# R3D900.net
KiCad netlist of a schematic drawn in Altium Designer
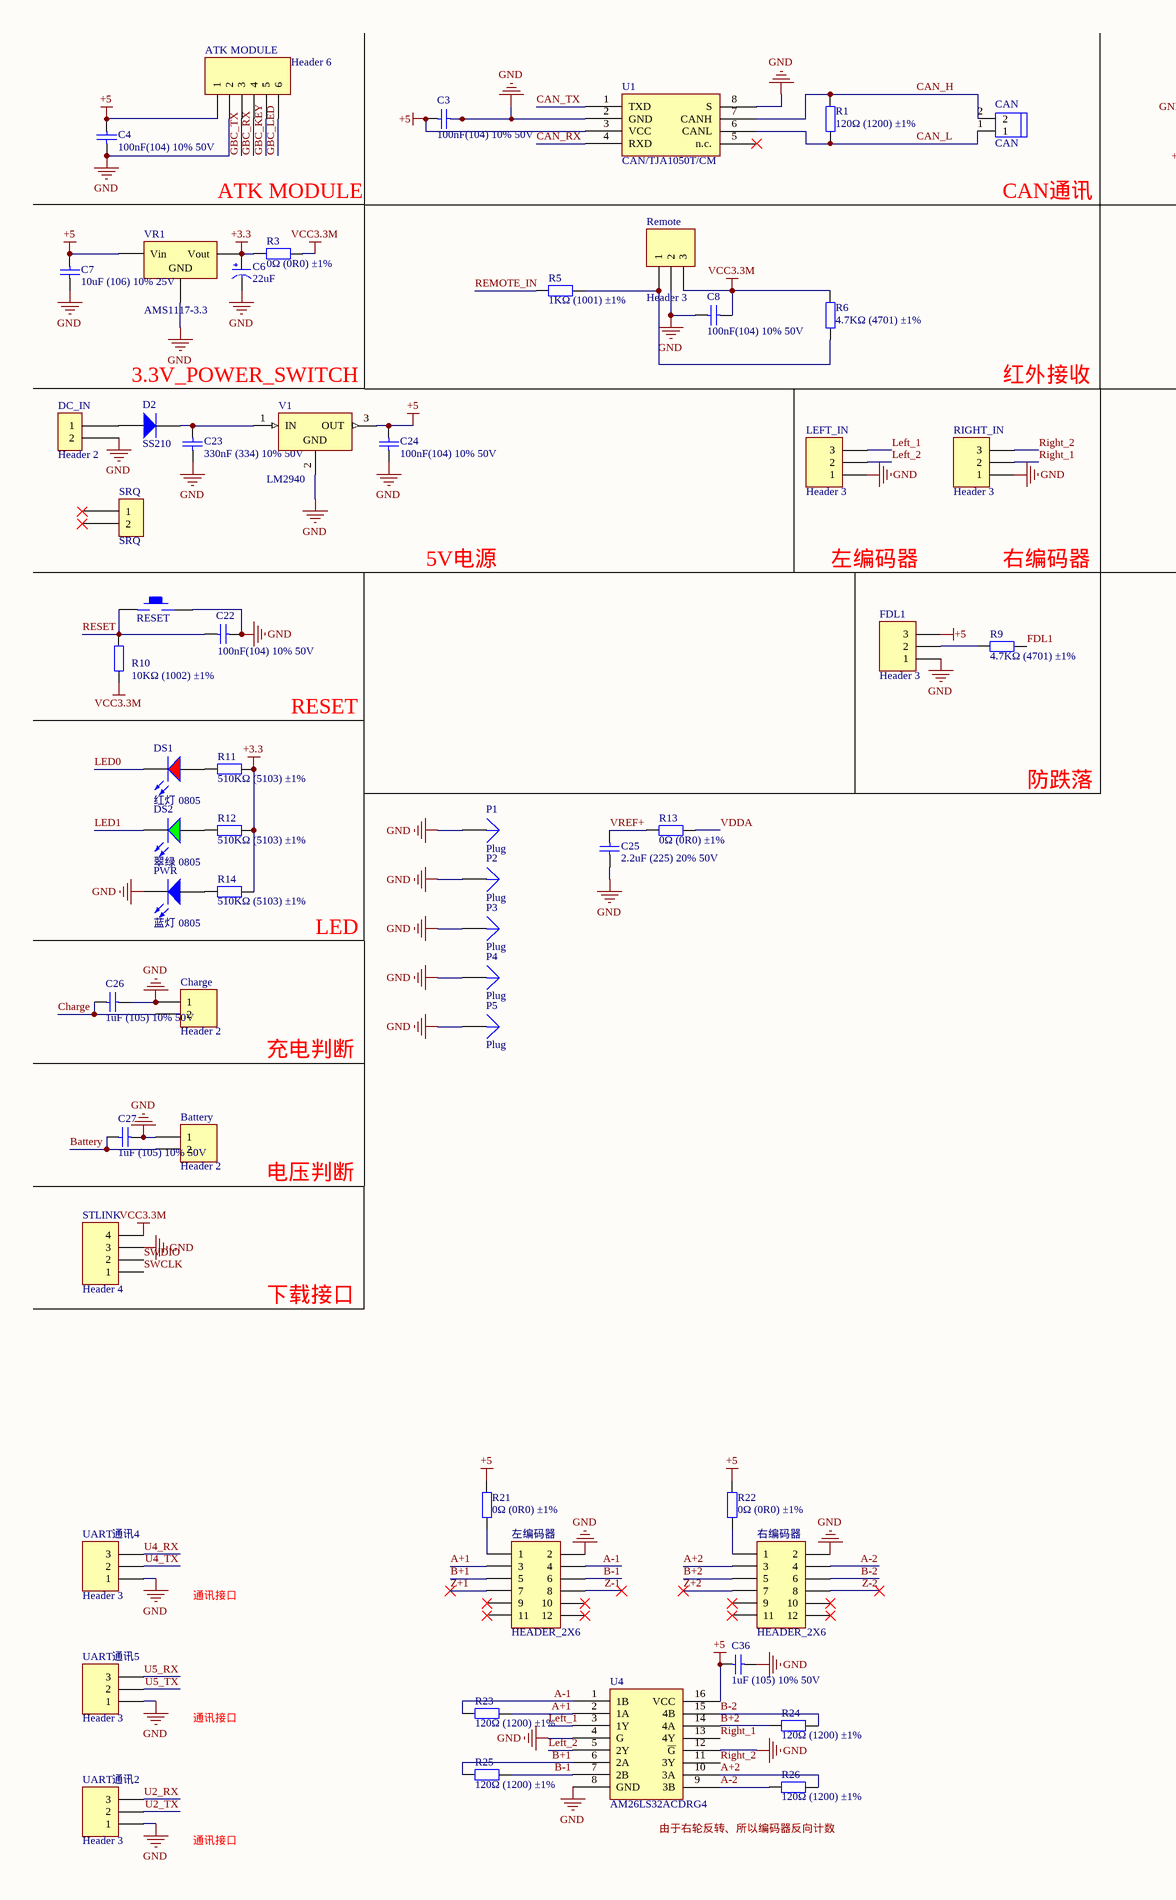
[diagram p0: R3D900.SchDoc, left]
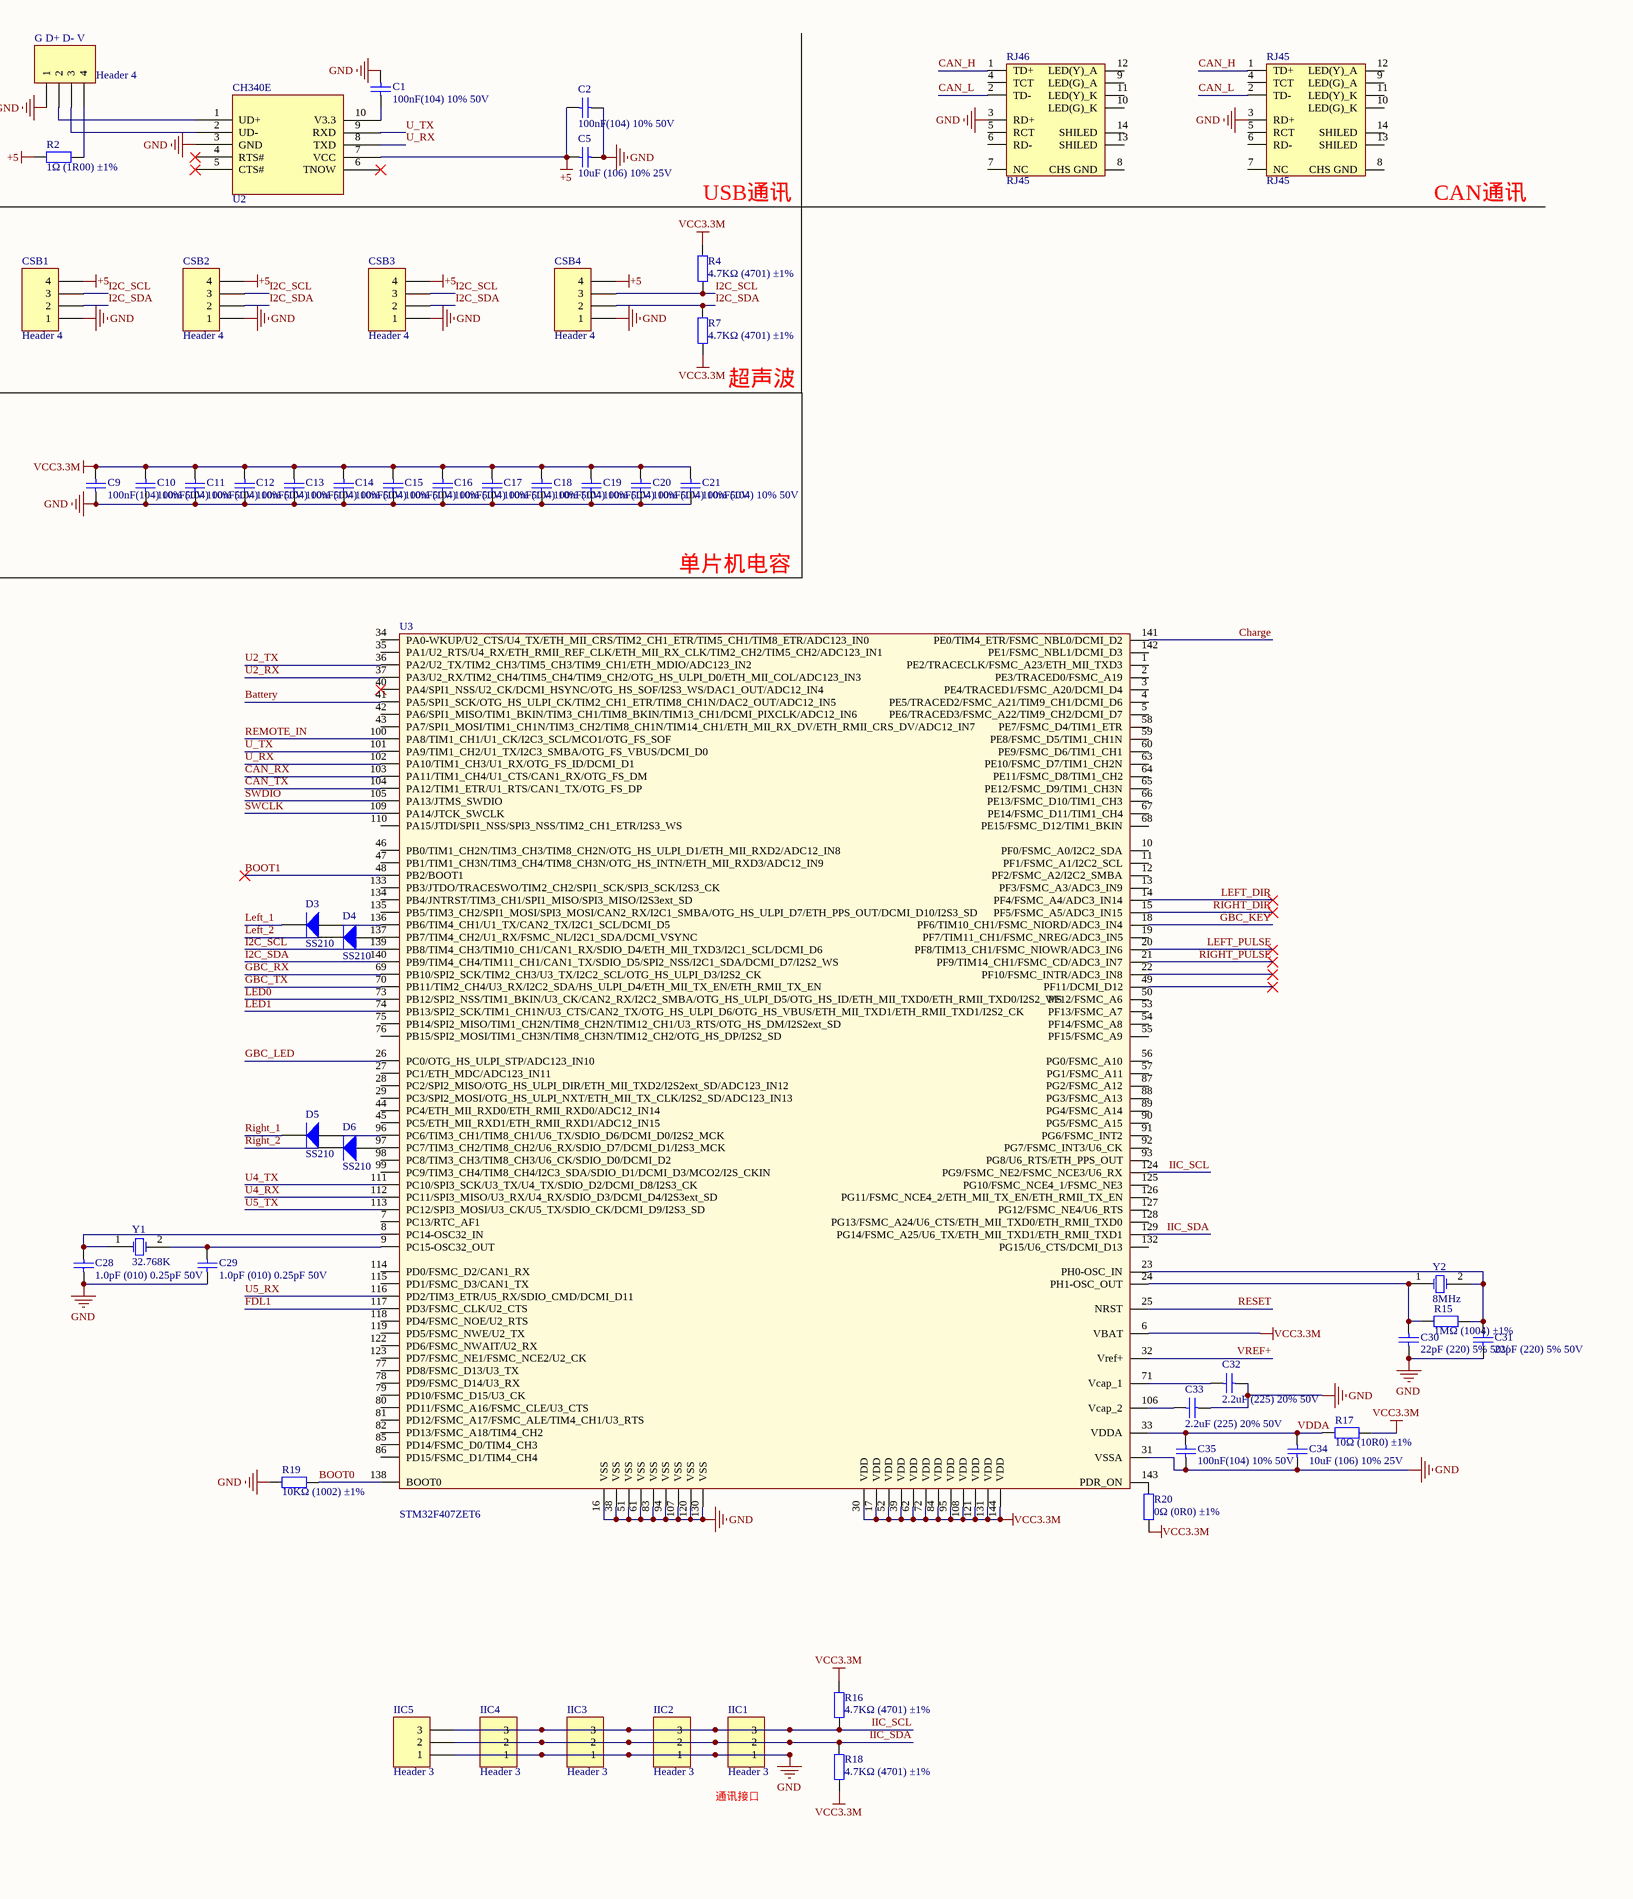
[diagram p1: R3D900.SchDoc, right]

(export (version "E")
  (design (tool "Eeschema 10.0.6"))
  (components
    (comp (ref "ATK MODULE")
      (value "Header 6")
      (footprint "HDR1X6")
      (description "Header, 6-Pin")
      (fields (field (name "PUBLISHER") "Altium Limited"))
      (libsource (lib "Miscellaneous Connectors") (part "Header 6"))
    )
    (comp (ref "Battery")
      (value "Header 2")
      (footprint "HDR1X2")
      (description "Header, 2-Pin")
      (fields (field (name "PUBLISHER") "Altium Limited"))
      (libsource (lib "Miscellaneous Connectors") (part "Header 2"))
    )
    (comp (ref "C1")
      (value "100nF(104) 10% 50V")
      (footprint "LC-0805_C")
      (description "贴片电容")
      (libsource (lib "Miscellaneous Devices LC") (part "0805 100nF(104) 10% 50V"))
    )
    (comp (ref "C2")
      (value "100nF(104) 10% 50V")
      (footprint "LC-0805_C")
      (description "贴片电容")
      (libsource (lib "Miscellaneous Devices LC") (part "0805 100nF(104) 10% 50V"))
    )
    (comp (ref "C3")
      (value "100nF(104) 10% 50V")
      (footprint "LC-0805_C")
      (description "贴片电容")
      (libsource (lib "Miscellaneous Devices LC") (part "0805 100nF(104) 10% 50V"))
    )
    (comp (ref "C4")
      (value "100nF(104) 10% 50V")
      (footprint "LC-0805_C")
      (description "贴片电容")
      (libsource (lib "Miscellaneous Devices LC") (part "0805 100nF(104) 10% 50V"))
    )
    (comp (ref "C5")
      (value "10uF (106) 10% 25V")
      (footprint "LC-0805_C")
      (description "贴片电容")
      (libsource (lib "Miscellaneous Devices LC") (part "0805 10uF (106) 10% 25V"))
    )
    (comp (ref "C6")
      (value "22uF")
      (footprint "CC6.56.5")
      (libsource (lib "Explorer STM32F407封装库") (part "CAP"))
    )
    (comp (ref "C7")
      (value "10uF (106) 10% 25V")
      (footprint "LC-0805_C")
      (description "贴片电容")
      (libsource (lib "Miscellaneous Devices LC") (part "0805 10uF (106) 10% 25V"))
    )
    (comp (ref "C8")
      (value "100nF(104) 10% 50V")
      (footprint "LC-0805_C")
      (description "贴片电容")
      (libsource (lib "Miscellaneous Devices LC") (part "0805 100nF(104) 10% 50V"))
    )
    (comp (ref "C9")
      (value "100nF(104) 10% 50V")
      (footprint "LC-0805_C")
      (description "贴片电容")
      (libsource (lib "Miscellaneous Devices LC") (part "0805 100nF(104) 10% 50V"))
    )
    (comp (ref "C10")
      (value "100nF(104) 10% 50V")
      (footprint "LC-0805_C")
      (description "贴片电容")
      (libsource (lib "Miscellaneous Devices LC") (part "0805 100nF(104) 10% 50V"))
    )
    (comp (ref "C11")
      (value "100nF(104) 10% 50V")
      (footprint "LC-0805_C")
      (description "贴片电容")
      (libsource (lib "Miscellaneous Devices LC") (part "0805 100nF(104) 10% 50V"))
    )
    (comp (ref "C12")
      (value "100nF(104) 10% 50V")
      (footprint "LC-0805_C")
      (description "贴片电容")
      (libsource (lib "Miscellaneous Devices LC") (part "0805 100nF(104) 10% 50V"))
    )
    (comp (ref "C13")
      (value "100nF(104) 10% 50V")
      (footprint "LC-0805_C")
      (description "贴片电容")
      (libsource (lib "Miscellaneous Devices LC") (part "0805 100nF(104) 10% 50V"))
    )
    (comp (ref "C14")
      (value "100nF(104) 10% 50V")
      (footprint "LC-0805_C")
      (description "贴片电容")
      (libsource (lib "Miscellaneous Devices LC") (part "0805 100nF(104) 10% 50V"))
    )
    (comp (ref "C15")
      (value "100nF(104) 10% 50V")
      (footprint "LC-0805_C")
      (description "贴片电容")
      (libsource (lib "Miscellaneous Devices LC") (part "0805 100nF(104) 10% 50V"))
    )
    (comp (ref "C16")
      (value "100nF(104) 10% 50V")
      (footprint "LC-0805_C")
      (description "贴片电容")
      (libsource (lib "Miscellaneous Devices LC") (part "0805 100nF(104) 10% 50V"))
    )
    (comp (ref "C17")
      (value "100nF(104) 10% 50V")
      (footprint "LC-0805_C")
      (description "贴片电容")
      (libsource (lib "Miscellaneous Devices LC") (part "0805 100nF(104) 10% 50V"))
    )
    (comp (ref "C18")
      (value "100nF(104) 10% 50V")
      (footprint "LC-0805_C")
      (description "贴片电容")
      (libsource (lib "Miscellaneous Devices LC") (part "0805 100nF(104) 10% 50V"))
    )
    (comp (ref "C19")
      (value "100nF(104) 10% 50V")
      (footprint "LC-0805_C")
      (description "贴片电容")
      (libsource (lib "Miscellaneous Devices LC") (part "0805 100nF(104) 10% 50V"))
    )
    (comp (ref "C20")
      (value "100nF(104) 10% 50V")
      (footprint "LC-0805_C")
      (description "贴片电容")
      (libsource (lib "Miscellaneous Devices LC") (part "0805 100nF(104) 10% 50V"))
    )
    (comp (ref "C21")
      (value "100nF(104) 10% 50V")
      (footprint "LC-0805_C")
      (description "贴片电容")
      (libsource (lib "Miscellaneous Devices LC") (part "0805 100nF(104) 10% 50V"))
    )
    (comp (ref "C22")
      (value "100nF(104) 10% 50V")
      (footprint "LC-0805_C")
      (description "贴片电容")
      (libsource (lib "Miscellaneous Devices LC") (part "0805 100nF(104) 10% 50V"))
    )
    (comp (ref "C23")
      (value "330nF (334) 10% 50V")
      (footprint "LC-0805_C")
      (description "贴片电容")
      (libsource (lib "Miscellaneous Devices LC") (part "0805 330nF (334) 10% 50V"))
    )
    (comp (ref "C24")
      (value "100nF(104) 10% 50V")
      (footprint "LC-0805_C")
      (description "贴片电容")
      (libsource (lib "Miscellaneous Devices LC") (part "0805 100nF(104) 10% 50V"))
    )
    (comp (ref "C25")
      (value "2.2uF (225) 20% 50V")
      (footprint "LC-0805_C")
      (description "贴片电容")
      (libsource (lib "Miscellaneous Devices LC") (part "0805 2.2uF (225) 20% 50V"))
    )
    (comp (ref "C26")
      (value "1uF (105) 10% 50V")
      (footprint "LC-0805_C")
      (description "贴片电容")
      (libsource (lib "Miscellaneous Devices LC") (part "0805 1uF (105) 10% 50V"))
    )
    (comp (ref "C27")
      (value "1uF (105) 10% 50V")
      (footprint "LC-0805_C")
      (description "贴片电容")
      (libsource (lib "Miscellaneous Devices LC") (part "0805 1uF (105) 10% 50V"))
    )
    (comp (ref "C28")
      (value "1.0pF (010) 0.25pF 50V")
      (footprint "LC-0805_C")
      (description "贴片电容")
      (libsource (lib "Miscellaneous Devices LC") (part "0805 1.0pF (010) 0.25pF 50V"))
    )
    (comp (ref "C29")
      (value "1.0pF (010) 0.25pF 50V")
      (footprint "LC-0805_C")
      (description "贴片电容")
      (libsource (lib "Miscellaneous Devices LC") (part "0805 1.0pF (010) 0.25pF 50V"))
    )
    (comp (ref "C30")
      (value "22pF (220) 5% 50V")
      (footprint "LC-0805_C")
      (description "贴片电容")
      (libsource (lib "Miscellaneous Devices LC") (part "0805 22pF (220) 5% 50V"))
    )
    (comp (ref "C31")
      (value "22pF (220) 5% 50V")
      (footprint "LC-0805_C")
      (description "贴片电容")
      (libsource (lib "Miscellaneous Devices LC") (part "0805 22pF (220) 5% 50V"))
    )
    (comp (ref "C32")
      (value "2.2uF (225) 20% 50V")
      (footprint "LC-0805_C")
      (description "贴片电容")
      (libsource (lib "Miscellaneous Devices LC") (part "0805 2.2uF (225) 20% 50V"))
    )
    (comp (ref "C33")
      (value "2.2uF (225) 20% 50V")
      (footprint "LC-0805_C")
      (description "贴片电容")
      (libsource (lib "Miscellaneous Devices LC") (part "0805 2.2uF (225) 20% 50V"))
    )
    (comp (ref "C34")
      (value "10uF (106) 10% 25V")
      (footprint "LC-0805_C")
      (description "贴片电容")
      (libsource (lib "Miscellaneous Devices LC") (part "0805 10uF (106) 10% 25V"))
    )
    (comp (ref "C35")
      (value "100nF(104) 10% 50V")
      (footprint "LC-0805_C")
      (description "贴片电容")
      (libsource (lib "Miscellaneous Devices LC") (part "0805 100nF(104) 10% 50V"))
    )
    (comp (ref "C36")
      (value "1uF (105) 10% 50V")
      (footprint "LC-0805_C")
      (description "贴片电容")
      (libsource (lib "Miscellaneous Devices LC") (part "0805 1uF (105) 10% 50V"))
    )
    (comp (ref "CAN")
      (value "CAN")
      (footprint "HEAD2L-0.8")
      (libsource (lib "Explorer STM32F407封装库") (part "HEAD2"))
    )
    (comp (ref "Charge")
      (value "Header 2")
      (footprint "HDR1X2")
      (description "Header, 2-Pin")
      (fields (field (name "PUBLISHER") "Altium Limited"))
      (libsource (lib "Miscellaneous Connectors") (part "Header 2"))
    )
    (comp (ref "CSB1")
      (value "Header 4")
      (footprint "HDR1X4")
      (description "Header, 4-Pin")
      (fields (field (name "PUBLISHER") "Altium Limited"))
      (libsource (lib "") (part "Header 4_1"))
    )
    (comp (ref "CSB2")
      (value "Header 4")
      (footprint "HDR1X4")
      (description "Header, 4-Pin")
      (fields (field (name "PUBLISHER") "Altium Limited"))
      (libsource (lib "") (part "Header 4_1"))
    )
    (comp (ref "CSB3")
      (value "Header 4")
      (footprint "HDR1X4")
      (description "Header, 4-Pin")
      (fields (field (name "PUBLISHER") "Altium Limited"))
      (libsource (lib "") (part "Header 4_1"))
    )
    (comp (ref "CSB4")
      (value "Header 4")
      (footprint "HDR1X4")
      (description "Header, 4-Pin")
      (fields (field (name "PUBLISHER") "Altium Limited"))
      (libsource (lib "") (part "Header 4_1"))
    )
    (comp (ref "D2")
      (value "SS210")
      (footprint "LC-SMA(DO-214AC)_S1")
      (description "二极管")
      (libsource (lib "Miscellaneous Devices LC") (part "SMA(DO-214AC) SS210"))
    )
    (comp (ref "D3")
      (value "SS210")
      (footprint "LC-SMA(DO-214AC)_S1")
      (description "二极管")
      (libsource (lib "Miscellaneous Devices LC") (part "SMA(DO-214AC) SS210"))
    )
    (comp (ref "D4")
      (value "SS210")
      (footprint "LC-SMA(DO-214AC)_S1")
      (description "二极管")
      (libsource (lib "Miscellaneous Devices LC") (part "SMA(DO-214AC) SS210"))
    )
    (comp (ref "D5")
      (value "SS210")
      (footprint "LC-SMA(DO-214AC)_S1")
      (description "二极管")
      (libsource (lib "Miscellaneous Devices LC") (part "SMA(DO-214AC) SS210"))
    )
    (comp (ref "D6")
      (value "SS210")
      (footprint "LC-SMA(DO-214AC)_S1")
      (description "二极管")
      (libsource (lib "Miscellaneous Devices LC") (part "SMA(DO-214AC) SS210"))
    )
    (comp (ref "DC_IN")
      (value "Header 2")
      (footprint "VH-2A - Circle Hole")
      (description "贴片2p座")
      (libsource (lib "AD_Chip_Y") (part "Header 2"))
    )
    (comp (ref "DS1")
      (value "红灯 0805")
      (footprint "LC-0805_LED_S1")
      (description "发光二极管")
      (libsource (lib "Miscellaneous Devices LC") (part "0805 红灯"))
    )
    (comp (ref "DS2")
      (value "翠绿 0805")
      (footprint "LC-0805_LED_S1")
      (description "发光二极管")
      (libsource (lib "Miscellaneous Devices LC") (part "0805 翠绿"))
    )
    (comp (ref "FDL1")
      (value "Header 3")
      (footprint "HDR1X3")
      (description "Header, 3-Pin")
      (fields (field (name "PUBLISHER") "Altium Limited"))
      (libsource (lib "Miscellaneous Connectors") (part "Header 3"))
    )
    (comp (ref "G D+ D- V")
      (value "Header 4")
      (footprint "HDR1X4")
      (description "Header, 4-Pin")
      (fields (field (name "PUBLISHER") "Altium Limited"))
      (libsource (lib "Miscellaneous Connectors") (part "Header 4"))
    )
    (comp (ref "IIC1")
      (value "Header 3")
      (footprint "HDR1X3")
      (description "Header, 3-Pin")
      (fields (field (name "PUBLISHER") "Altium Limited"))
      (libsource (lib "Miscellaneous Connectors") (part "Header 3"))
    )
    (comp (ref "IIC2")
      (value "Header 3")
      (footprint "HDR1X3")
      (description "Header, 3-Pin")
      (fields (field (name "PUBLISHER") "Altium Limited"))
      (libsource (lib "Miscellaneous Connectors") (part "Header 3"))
    )
    (comp (ref "IIC3")
      (value "Header 3")
      (footprint "HDR1X3")
      (description "Header, 3-Pin")
      (fields (field (name "PUBLISHER") "Altium Limited"))
      (libsource (lib "Miscellaneous Connectors") (part "Header 3"))
    )
    (comp (ref "IIC4")
      (value "Header 3")
      (footprint "HDR1X3")
      (description "Header, 3-Pin")
      (fields (field (name "PUBLISHER") "Altium Limited"))
      (libsource (lib "Miscellaneous Connectors") (part "Header 3"))
    )
    (comp (ref "IIC5")
      (value "Header 3")
      (footprint "HDR1X3")
      (description "Header, 3-Pin")
      (fields (field (name "PUBLISHER") "Altium Limited"))
      (libsource (lib "Miscellaneous Connectors") (part "Header 3"))
    )
    (comp (ref "LEFT_IN")
      (value "Header 3")
      (footprint "HDR1X3")
      (description "Header, 3-Pin")
      (fields (field (name "PUBLISHER") "Altium Limited"))
      (libsource (lib "Miscellaneous Connectors") (part "Header 3"))
    )
    (comp (ref "P1")
      (value "Plug")
      (footprint "PIN1")
      (fields (field (name "PUBLISHER") "Altium Limited"))
      (libsource (lib "Miscellaneous Connectors") (part "Plug"))
    )
    (comp (ref "P2")
      (value "Plug")
      (footprint "PIN1")
      (fields (field (name "PUBLISHER") "Altium Limited"))
      (libsource (lib "Miscellaneous Connectors") (part "Plug"))
    )
    (comp (ref "P3")
      (value "Plug")
      (footprint "PIN1")
      (fields (field (name "PUBLISHER") "Altium Limited"))
      (libsource (lib "Miscellaneous Connectors") (part "Plug"))
    )
    (comp (ref "P4")
      (value "Plug")
      (footprint "PIN1")
      (fields (field (name "PUBLISHER") "Altium Limited"))
      (libsource (lib "Miscellaneous Connectors") (part "Plug"))
    )
    (comp (ref "P5")
      (value "Plug")
      (footprint "PIN1")
      (fields (field (name "PUBLISHER") "Altium Limited"))
      (libsource (lib "Miscellaneous Connectors") (part "Plug"))
    )
    (comp (ref "PWR")
      (value "蓝灯 0805")
      (footprint "LC-0805_LED_S1")
      (description "发光二极管")
      (libsource (lib "Miscellaneous Devices LC") (part "0805 蓝灯"))
    )
    (comp (ref "R1")
      (value "120Ω (1200) ±1%")
      (footprint "LC-0805_R")
      (description "贴片电阻")
      (libsource (lib "") (part "0805 120Ω (1200) 1%_1"))
    )
    (comp (ref "R2")
      (value "1Ω (1R00) ±1%")
      (footprint "LC-0603_R")
      (description "贴片电阻")
      (libsource (lib "Miscellaneous Devices LC") (part "0603 1Ω (1R00) 1%"))
    )
    (comp (ref "R3")
      (value "0Ω (0R0) ±1%")
      (footprint "LC-0603_R")
      (description "贴片电阻")
      (libsource (lib "") (part "0603 0Ω (0R0) 1%_1"))
    )
    (comp (ref "R4")
      (value "4.7KΩ (4701) ±1%")
      (footprint "LC-0805_R")
      (description "贴片电阻")
      (libsource (lib "Miscellaneous Devices LC") (part "0805 4.7KΩ (4701) 1%"))
    )
    (comp (ref "R5")
      (value "1KΩ (1001) ±1%")
      (footprint "LC-0805_R")
      (description "贴片电阻")
      (libsource (lib "Miscellaneous Devices LC") (part "0805 1KΩ (1001) 1%"))
    )
    (comp (ref "R6")
      (value "4.7KΩ (4701) ±1%")
      (footprint "LC-0805_R")
      (description "贴片电阻")
      (libsource (lib "Miscellaneous Devices LC") (part "0805 4.7KΩ (4701) 1%"))
    )
    (comp (ref "R7")
      (value "4.7KΩ (4701) ±1%")
      (footprint "LC-0805_R")
      (description "贴片电阻")
      (libsource (lib "Miscellaneous Devices LC") (part "0805 4.7KΩ (4701) 1%"))
    )
    (comp (ref "R9")
      (value "4.7KΩ (4701) ±1%")
      (footprint "LC-0805_R")
      (description "贴片电阻")
      (libsource (lib "") (part "0805 4.7KΩ (4701) 1%_1"))
    )
    (comp (ref "R10")
      (value "10KΩ (1002) ±1%")
      (footprint "LC-0805_R")
      (description "贴片电阻")
      (libsource (lib "") (part "0805 10KΩ (1002) 1%_1"))
    )
    (comp (ref "R11")
      (value "510KΩ (5103) ±1%")
      (footprint "LC-0805_R")
      (description "贴片电阻")
      (libsource (lib "Miscellaneous Devices LC") (part "0805 510KΩ (5103) 1%"))
    )
    (comp (ref "R12")
      (value "510KΩ (5103) ±1%")
      (footprint "LC-0805_R")
      (description "贴片电阻")
      (libsource (lib "Miscellaneous Devices LC") (part "0805 510KΩ (5103) 1%"))
    )
    (comp (ref "R13")
      (value "0Ω (0R0) ±1%")
      (footprint "LC-0603_R")
      (description "贴片电阻")
      (libsource (lib "") (part "0603 0Ω (0R0) 1%_1"))
    )
    (comp (ref "R14")
      (value "510KΩ (5103) ±1%")
      (footprint "LC-0805_R")
      (description "贴片电阻")
      (libsource (lib "Miscellaneous Devices LC") (part "0805 510KΩ (5103) 1%"))
    )
    (comp (ref "R15")
      (value "1MΩ (1004) ±1%")
      (footprint "LC-0805_R")
      (description "贴片电阻")
      (libsource (lib "Miscellaneous Devices LC") (part "0805 1MΩ (1004) 1%"))
    )
    (comp (ref "R16")
      (value "4.7KΩ (4701) ±1%")
      (footprint "LC-0805_R")
      (description "贴片电阻")
      (libsource (lib "Miscellaneous Devices LC") (part "0805 4.7KΩ (4701) 1%"))
    )
    (comp (ref "R17")
      (value "10Ω (10R0) ±1%")
      (footprint "LC-0805_R")
      (description "贴片电阻")
      (libsource (lib "Miscellaneous Devices LC") (part "0805 10Ω (10R0) 1%"))
    )
    (comp (ref "R18")
      (value "4.7KΩ (4701) ±1%")
      (footprint "LC-0805_R")
      (description "贴片电阻")
      (libsource (lib "Miscellaneous Devices LC") (part "0805 4.7KΩ (4701) 1%"))
    )
    (comp (ref "R19")
      (value "10KΩ (1002) ±1%")
      (footprint "LC-0805_R")
      (description "贴片电阻")
      (libsource (lib "Miscellaneous Devices LC") (part "0805 10KΩ (1002) 1%"))
    )
    (comp (ref "R20")
      (value "0Ω (0R0) ±1%")
      (footprint "LC-0603_R")
      (description "贴片电阻")
      (libsource (lib "Miscellaneous Devices LC") (part "0603 0Ω (0R0) 1%"))
    )
    (comp (ref "R21")
      (value "0Ω (0R0) ±1%")
      (footprint "LC-0603_R")
      (description "贴片电阻")
      (libsource (lib "Miscellaneous Devices LC") (part "0603 0Ω (0R0) 1%"))
    )
    (comp (ref "R22")
      (value "0Ω (0R0) ±1%")
      (footprint "LC-0603_R")
      (description "贴片电阻")
      (libsource (lib "Miscellaneous Devices LC") (part "0603 0Ω (0R0) 1%"))
    )
    (comp (ref "R23")
      (value "120Ω (1200) ±1%")
      (footprint "LC-0805_R")
      (description "贴片电阻")
      (libsource (lib "Miscellaneous Devices LC") (part "0805 120Ω (1200) 1%"))
    )
    (comp (ref "R24")
      (value "120Ω (1200) ±1%")
      (footprint "LC-0805_R")
      (description "贴片电阻")
      (libsource (lib "Miscellaneous Devices LC") (part "0805 120Ω (1200) 1%"))
    )
    (comp (ref "R25")
      (value "120Ω (1200) ±1%")
      (footprint "LC-0805_R")
      (description "贴片电阻")
      (libsource (lib "Miscellaneous Devices LC") (part "0805 120Ω (1200) 1%"))
    )
    (comp (ref "R26")
      (value "120Ω (1200) ±1%")
      (footprint "LC-0805_R")
      (description "贴片电阻")
      (libsource (lib "Miscellaneous Devices LC") (part "0805 120Ω (1200) 1%"))
    )
    (comp (ref "Remote")
      (value "Header 3")
      (footprint "HDR1X3")
      (description "Header, 3-Pin")
      (fields (field (name "PUBLISHER") "Altium Limited"))
      (libsource (lib "") (part "Header 3_1"))
    )
    (comp (ref "RESET") (value "KEY_M") (footprint "KEY_M") (libsource (lib "AD_Chip_Y") (part "KEY_M")))
    (comp (ref "RIGHT_IN")
      (value "Header 3")
      (footprint "HDR1X3")
      (description "Header, 3-Pin")
      (fields (field (name "PUBLISHER") "Altium Limited"))
      (libsource (lib "Miscellaneous Connectors") (part "Header 3"))
    )
    (comp (ref "RJ45") (value "RJ45") (footprint "RJ45") (libsource (lib "AD_Chip_Y") (part "RJ45")))
    (comp (ref "RJ46") (value "RJ45") (footprint "RJ45") (libsource (lib "AD_Chip_Y") (part "RJ45")))
    (comp (ref "SRQ") (value "SRQ") (footprint "Hot_Clear") (libsource (lib "AD_Chip_Y") (part "Hot_Clear")))
    (comp (ref "STLINK")
      (value "Header 4")
      (footprint "HDR1X4")
      (description "Header, 4-Pin")
      (fields (field (name "PUBLISHER") "Altium Limited"))
      (libsource (lib "") (part "Header 4_1"))
    )
    (comp (ref "U1")
      (value "CAN/TJA1050T/CM")
      (footprint "LC-SOIC-8_150mil")
      (description "CAN")
      (libsource (lib "Miscellaneous Devices LC") (part "CAN/TJA1050T/CM"))
    )
    (comp (ref "U2")
      (value "CH340E")
      (footprint "LC-MSOP-10")
      (description "USB")
      (libsource (lib "AD_Chip_Y") (part "CH340E"))
    )
    (comp (ref "U3")
      (value "STM32F407ZET6")
      (footprint "LQFP144")
      (libsource (lib "Explorer STM32F407封装库") (part "STM32F407ZET6"))
    )
    (comp (ref "U4")
      (value "AM26LS32ACDRG4")
      (footprint "LC-SOIC-16_150mil")
      (description "接口芯片")
      (libsource (lib "Miscellaneous Devices LC") (part "AM26LS32ACDRG4"))
    )
    (comp (ref "UART通讯2")
      (value "Header 3")
      (footprint "HDR1X3")
      (description "Header, 3-Pin")
      (fields (field (name "PUBLISHER") "Altium Limited"))
      (libsource (lib "Miscellaneous Connectors") (part "Header 3"))
    )
    (comp (ref "UART通讯4")
      (value "Header 3")
      (footprint "HDR1X3")
      (description "Header, 3-Pin")
      (fields (field (name "PUBLISHER") "Altium Limited"))
      (libsource (lib "Miscellaneous Connectors") (part "Header 3"))
    )
    (comp (ref "UART通讯5")
      (value "Header 3")
      (footprint "HDR1X3")
      (description "Header, 3-Pin")
      (fields (field (name "PUBLISHER") "Altium Limited"))
      (libsource (lib "Miscellaneous Connectors") (part "Header 3"))
    )
    (comp (ref "V1")
      (value "LM2940")
      (footprint "LC-TO-220(TO-220-3)")
      (description "Power Chip")
      (libsource (lib "AD_Chip_Y") (part "LM2940"))
    )
    (comp (ref "VR1")
      (value "AMS1117-3.3")
      (footprint "LC-SOT-223")
      (description "低压差线性稳压(LDO)")
      (libsource (lib "Miscellaneous Devices LC") (part "SOT-223 AMS1117-3.3"))
    )
    (comp (ref "Y1")
      (value "32.768K")
      (footprint "R38")
      (description "Crystal Oscillator")
      (fields (field (name "PUBLISHER") "Altium Limited"))
      (libsource (lib "Miscellaneous Devices") (part "XTAL"))
    )
    (comp (ref "Y2")
      (value "8MHz")
      (footprint "LC-HC-49SMD")
      (description "Crystal Oscillator")
      (fields (field (name "PUBLISHER") "Altium Limited"))
      (libsource (lib "AD_Chip_Y") (part "XTAL"))
    )
    (comp (ref "右编码器")
      (value "HEADER_2X6")
      (footprint "PHB_2x6_2.0")
      (description "Header, 6-Pin, Dual row")
      (fields (field (name "PUBLISHER") "Altium Limited"))
      (libsource (lib "AD_Chip_Y") (part "HEADER_2X6"))
    )
    (comp (ref "左编码器")
      (value "HEADER_2X6")
      (footprint "PHB_2x6_2.0")
      (description "Header, 6-Pin, Dual row")
      (fields (field (name "PUBLISHER") "Altium Limited"))
      (libsource (lib "AD_Chip_Y") (part "HEADER_2X6"))
    )
  )
  (nets
    (net (code "1") (name "+3.3") (class "Default")
      (node (ref "C6") (pin "1") (pinfunction "VCC_1") (pintype "passive"))
      (node (ref "R11") (pin "2") (pinfunction "2_2") (pintype "passive"))
      (node (ref "R12") (pin "2") (pinfunction "2_2") (pintype "passive"))
      (node (ref "R14") (pin "2") (pinfunction "2_2") (pintype "passive"))
      (node (ref "R3") (pin "1") (pinfunction "1_1") (pintype "passive"))
      (node (ref "VR1") (pin "2") (pinfunction "Vout_2") (pintype "passive"))
    )
    (net (code "2") (name "+5") (class "Default")
      (node (ref "ATK MODULE") (pin "1") (pinfunction "1_1") (pintype "passive"))
      (node (ref "C2") (pin "1") (pinfunction "1_1") (pintype "passive"))
      (node (ref "C24") (pin "2") (pinfunction "2_2") (pintype "passive"))
      (node (ref "C3") (pin "1") (pinfunction "1_1") (pintype "passive"))
      (node (ref "C36") (pin "2") (pinfunction "2_2") (pintype "passive"))
      (node (ref "C4") (pin "2") (pinfunction "2_2") (pintype "passive"))
      (node (ref "C5") (pin "1") (pinfunction "1_1") (pintype "passive"))
      (node (ref "C7") (pin "2") (pinfunction "2_2") (pintype "passive"))
      (node (ref "CSB1") (pin "4") (pinfunction "4_4") (pintype "passive"))
      (node (ref "CSB2") (pin "4") (pinfunction "4_4") (pintype "passive"))
      (node (ref "CSB3") (pin "4") (pinfunction "4_4") (pintype "passive"))
      (node (ref "CSB4") (pin "4") (pinfunction "4_4") (pintype "passive"))
      (node (ref "FDL1") (pin "3") (pinfunction "3_3") (pintype "passive"))
      (node (ref "R2") (pin "1") (pinfunction "1_1") (pintype "passive"))
      (node (ref "R21") (pin "2") (pinfunction "2_2") (pintype "passive"))
      (node (ref "R22") (pin "2") (pinfunction "2_2") (pintype "passive"))
      (node (ref "U1") (pin "3") (pinfunction "VCC_3") (pintype "passive"))
      (node (ref "U2") (pin "7") (pinfunction "VCC_7") (pintype "passive"))
      (node (ref "U4") (pin "16") (pinfunction "VCC_16") (pintype "passive"))
      (node (ref "V1") (pin "3") (pinfunction "OUT_3") (pintype "output"))
      (node (ref "VR1") (pin "3") (pinfunction "Vin_3") (pintype "passive"))
    )
    (net (code "3") (name "/A+1") (class "Default")
      (node (ref "R23") (pin "1") (pinfunction "1_1") (pintype "passive"))
      (node (ref "U4") (pin "2") (pinfunction "1A_2") (pintype "passive"))
      (node (ref "左编码器") (pin "3") (pinfunction "3_3") (pintype "passive"))
    )
    (net (code "4") (name "/A+2") (class "Default")
      (node (ref "R26") (pin "1") (pinfunction "1_1") (pintype "passive"))
      (node (ref "U4") (pin "10") (pinfunction "3A_10") (pintype "passive"))
      (node (ref "右编码器") (pin "3") (pinfunction "3_3") (pintype "passive"))
    )
    (net (code "5") (name "/A-1") (class "Default")
      (node (ref "R23") (pin "2") (pinfunction "2_2") (pintype "passive"))
      (node (ref "U4") (pin "1") (pinfunction "1B_1") (pintype "passive"))
      (node (ref "左编码器") (pin "4") (pinfunction "4_4") (pintype "passive"))
    )
    (net (code "6") (name "/A-2") (class "Default")
      (node (ref "R26") (pin "2") (pinfunction "2_2") (pintype "passive"))
      (node (ref "U4") (pin "9") (pinfunction "3B_9") (pintype "passive"))
      (node (ref "右编码器") (pin "4") (pinfunction "4_4") (pintype "passive"))
    )
    (net (code "7") (name "/B+1") (class "Default")
      (node (ref "R25") (pin "2") (pinfunction "2_2") (pintype "passive"))
      (node (ref "U4") (pin "6") (pinfunction "2A_6") (pintype "passive"))
      (node (ref "左编码器") (pin "5") (pinfunction "5_5") (pintype "passive"))
    )
    (net (code "8") (name "/B+2") (class "Default")
      (node (ref "R24") (pin "2") (pinfunction "2_2") (pintype "passive"))
      (node (ref "U4") (pin "14") (pinfunction "4A_14") (pintype "passive"))
      (node (ref "右编码器") (pin "5") (pinfunction "5_5") (pintype "passive"))
    )
    (net (code "9") (name "/B-1") (class "Default")
      (node (ref "R25") (pin "1") (pinfunction "1_1") (pintype "passive"))
      (node (ref "U4") (pin "7") (pinfunction "2B_7") (pintype "passive"))
      (node (ref "左编码器") (pin "6") (pinfunction "6_6") (pintype "passive"))
    )
    (net (code "10") (name "/B-2") (class "Default")
      (node (ref "R24") (pin "1") (pinfunction "1_1") (pintype "passive"))
      (node (ref "U4") (pin "15") (pinfunction "4B_15") (pintype "passive"))
      (node (ref "右编码器") (pin "6") (pinfunction "6_6") (pintype "passive"))
    )
    (net (code "11") (name "/BOOT0") (class "Default")
      (node (ref "R19") (pin "2") (pinfunction "2_2") (pintype "passive"))
      (node (ref "U3") (pin "138") (pinfunction "BOOT0_138") (pintype "passive"))
    )
    (net (code "12") (name "/BOOT1") (class "Default")
      (node (ref "U3") (pin "48") (pinfunction "PB2/BOOT1_48") (pintype "passive+no_connect"))
    )
    (net (code "13") (name "/Battery") (class "Default")
      (node (ref "Battery") (pin "2") (pinfunction "2_2") (pintype "passive"))
      (node (ref "C27") (pin "2") (pinfunction "2_2") (pintype "passive"))
      (node (ref "U3") (pin "41") (pinfunction "PA5/SPI1_SCK/OTG_HS_ULPI_CK/TIM2_CH1_ETR/TIM8_CH1N/DAC2_OUT/ADC12_IN5_41") (pintype "passive"))
    )
    (net (code "14") (name "/CAN_H") (class "Default")
      (node (ref "CAN") (pin "2") (pinfunction "2_2") (pintype "passive"))
      (node (ref "R1") (pin "2") (pinfunction "2_2") (pintype "passive"))
      (node (ref "RJ45") (pin "1") (pinfunction "TD+_1") (pintype "passive"))
      (node (ref "RJ46") (pin "1") (pinfunction "TD+_1") (pintype "passive"))
      (node (ref "U1") (pin "7") (pinfunction "CANH_7") (pintype "passive"))
    )
    (net (code "15") (name "/CAN_L") (class "Default")
      (node (ref "CAN") (pin "1") (pinfunction "1_1") (pintype "passive"))
      (node (ref "R1") (pin "1") (pinfunction "1_1") (pintype "passive"))
      (node (ref "RJ45") (pin "2") (pinfunction "TD-_2") (pintype "passive"))
      (node (ref "RJ46") (pin "2") (pinfunction "TD-_2") (pintype "passive"))
      (node (ref "U1") (pin "6") (pinfunction "CANL_6") (pintype "passive"))
    )
    (net (code "16") (name "/CAN_RX") (class "Default")
      (node (ref "U1") (pin "4") (pinfunction "RXD_4") (pintype "passive"))
      (node (ref "U3") (pin "103") (pinfunction "PA11/TIM1_CH4/U1_CTS/CAN1_RX/OTG_FS_DM_103") (pintype "passive"))
    )
    (net (code "17") (name "/CAN_TX") (class "Default")
      (node (ref "U1") (pin "1") (pinfunction "TXD_1") (pintype "passive"))
      (node (ref "U3") (pin "104") (pinfunction "PA12/TIM1_ETR/U1_RTS/CAN1_TX/OTG_FS_DP_104") (pintype "passive"))
    )
    (net (code "18") (name "/Charge") (class "Default")
      (node (ref "C26") (pin "2") (pinfunction "2_2") (pintype "passive"))
      (node (ref "Charge") (pin "2") (pinfunction "2_2") (pintype "passive"))
      (node (ref "U3") (pin "141") (pinfunction "PE0/TIM4_ETR/FSMC_NBL0/DCMI_D2_141") (pintype "passive"))
    )
    (net (code "19") (name "/FDL1") (class "Default")
      (node (ref "R9") (pin "2") (pinfunction "2_2") (pintype "passive"))
      (node (ref "U3") (pin "117") (pinfunction "PD3/FSMC_CLK/U2_CTS_117") (pintype "passive"))
    )
    (net (code "20") (name "/GBC_KEY") (class "Default")
      (node (ref "ATK MODULE") (pin "5") (pinfunction "5_5") (pintype "passive"))
      (node (ref "U3") (pin "18") (pinfunction "PF6/TIM10_CH1/FSMC_NIORD/ADC3_IN4_18") (pintype "passive"))
    )
    (net (code "21") (name "/GBC_LED") (class "Default")
      (node (ref "ATK MODULE") (pin "6") (pinfunction "6_6") (pintype "passive"))
      (node (ref "U3") (pin "26") (pinfunction "PC0/OTG_HS_ULPI_STP/ADC123_IN10_26") (pintype "passive"))
    )
    (net (code "22") (name "/GBC_RX") (class "Default")
      (node (ref "ATK MODULE") (pin "4") (pinfunction "4_4") (pintype "passive"))
      (node (ref "U3") (pin "69") (pinfunction "PB10/SPI2_SCK/TIM2_CH3/U3_TX/I2C2_SCL/OTG_HS_ULPI_D3/I2S2_CK_69") (pintype "passive"))
    )
    (net (code "23") (name "/GBC_TX") (class "Default")
      (node (ref "ATK MODULE") (pin "3") (pinfunction "3_3") (pintype "passive"))
      (node (ref "U3") (pin "70") (pinfunction "PB11/TIM2_CH4/U3_RX/I2C2_SDA/HS_ULPI_D4/ETH_MII_TX_EN/ETH_RMII_TX_EN_70") (pintype "passive"))
    )
    (net (code "24") (name "/I2C_SCL") (class "Default")
      (node (ref "CSB1") (pin "3") (pinfunction "3_3") (pintype "passive"))
      (node (ref "CSB2") (pin "3") (pinfunction "3_3") (pintype "passive"))
      (node (ref "CSB3") (pin "3") (pinfunction "3_3") (pintype "passive"))
      (node (ref "CSB4") (pin "3") (pinfunction "3_3") (pintype "passive"))
      (node (ref "R4") (pin "1") (pinfunction "1_1") (pintype "passive"))
      (node (ref "U3") (pin "139") (pinfunction "PB8/TIM4_CH3/TIM10_CH1/CAN1_RX/SDIO_D4/ETH_MII_TXD3/I2C1_SCL/DCMI_D6_139") (pintype "passive"))
    )
    (net (code "25") (name "/I2C_SDA") (class "Default")
      (node (ref "CSB1") (pin "2") (pinfunction "2_2") (pintype "passive"))
      (node (ref "CSB2") (pin "2") (pinfunction "2_2") (pintype "passive"))
      (node (ref "CSB3") (pin "2") (pinfunction "2_2") (pintype "passive"))
      (node (ref "CSB4") (pin "2") (pinfunction "2_2") (pintype "passive"))
      (node (ref "R7") (pin "2") (pinfunction "2_2") (pintype "passive"))
      (node (ref "U3") (pin "140") (pinfunction "PB9/TIM4_CH4/TIM11_CH1/CAN1_TX/SDIO_D5/SPI2_NSS/I2C1_SDA/DCMI_D7/I2S2_WS_140") (pintype "passive"))
    )
    (net (code "26") (name "/IIC_SCL") (class "Default")
      (node (ref "IIC1") (pin "3") (pinfunction "3_3") (pintype "passive"))
      (node (ref "IIC2") (pin "3") (pinfunction "3_3") (pintype "passive"))
      (node (ref "IIC3") (pin "3") (pinfunction "3_3") (pintype "passive"))
      (node (ref "IIC4") (pin "3") (pinfunction "3_3") (pintype "passive"))
      (node (ref "IIC5") (pin "3") (pinfunction "3_3") (pintype "passive"))
      (node (ref "R16") (pin "1") (pinfunction "1_1") (pintype "passive"))
      (node (ref "U3") (pin "124") (pinfunction "PG9/FSMC_NE2/FSMC_NCE3/U6_RX_124") (pintype "passive"))
    )
    (net (code "27") (name "/IIC_SDA") (class "Default")
      (node (ref "IIC1") (pin "2") (pinfunction "2_2") (pintype "passive"))
      (node (ref "IIC2") (pin "2") (pinfunction "2_2") (pintype "passive"))
      (node (ref "IIC3") (pin "2") (pinfunction "2_2") (pintype "passive"))
      (node (ref "IIC4") (pin "2") (pinfunction "2_2") (pintype "passive"))
      (node (ref "IIC5") (pin "2") (pinfunction "2_2") (pintype "passive"))
      (node (ref "R18") (pin "2") (pinfunction "2_2") (pintype "passive"))
      (node (ref "U3") (pin "129") (pinfunction "PG14/FSMC_A25/U6_TX/ETH_MII_TXD1/ETH_RMII_TXD1_129") (pintype "passive"))
    )
    (net (code "28") (name "/LED0") (class "Default")
      (node (ref "DS1") (pin "K") (pinfunction "K_K") (pintype "passive"))
      (node (ref "U3") (pin "73") (pinfunction "PB12/SPI2_NSS/TIM1_BKIN/U3_CK/CAN2_RX/I2C2_SMBA/OTG_HS_ULPI_D5/OTG_HS_ID/ETH_MII_TXD0/ETH_RMII_TXD0/I2S2_WS_73") (pintype "passive"))
    )
    (net (code "29") (name "/LED1") (class "Default")
      (node (ref "DS2") (pin "K") (pinfunction "K_K") (pintype "passive"))
      (node (ref "U3") (pin "74") (pinfunction "PB13/SPI2_SCK/TIM1_CH1N/U3_CTS/CAN2_TX/OTG_HS_ULPI_D6/OTG_HS_VBUS/ETH_MII_TXD1/ETH_RMII_TXD1/I2S2_CK_74") (pintype "passive"))
    )
    (net (code "30") (name "/LEFT_DIR") (class "Default")
      (node (ref "U3") (pin "14") (pinfunction "PF4/FSMC_A4/ADC3_IN14_14") (pintype "passive+no_connect"))
    )
    (net (code "31") (name "/LEFT_PULSE") (class "Default")
      (node (ref "U3") (pin "20") (pinfunction "PF8/TIM13_CH1/FSMC_NIOWR/ADC3_IN6_20") (pintype "passive+no_connect"))
    )
    (net (code "32") (name "/Left_1") (class "Default")
      (node (ref "D3") (pin "2") (pinfunction "K_2") (pintype "passive"))
      (node (ref "LEFT_IN") (pin "3") (pinfunction "3_3") (pintype "passive"))
      (node (ref "U4") (pin "3") (pinfunction "1Y_3") (pintype "passive"))
    )
    (net (code "33") (name "/Left_2") (class "Default")
      (node (ref "D4") (pin "2") (pinfunction "K_2") (pintype "passive"))
      (node (ref "LEFT_IN") (pin "2") (pinfunction "2_2") (pintype "passive"))
      (node (ref "U4") (pin "5") (pinfunction "2Y_5") (pintype "passive"))
    )
    (net (code "34") (name "/REMOTE_IN") (class "Default")
      (node (ref "R5") (pin "1") (pinfunction "1_1") (pintype "passive"))
      (node (ref "U3") (pin "100") (pinfunction "PA8/TIM1_CH1/U1_CK/I2C3_SCL/MCO1/OTG_FS_SOF_100") (pintype "passive"))
    )
    (net (code "35") (name "/RESET") (class "Default")
      (node (ref "C22") (pin "2") (pinfunction "2_2") (pintype "passive"))
      (node (ref "R10") (pin "2") (pinfunction "2_2") (pintype "passive"))
      (node (ref "RESET") (pin "1") (pinfunction "1_1") (pintype "passive"))
      (node (ref "U3") (pin "25") (pinfunction "NRST_25") (pintype "passive"))
    )
    (net (code "36") (name "/RIGHT_DIR") (class "Default")
      (node (ref "U3") (pin "15") (pinfunction "PF5/FSMC_A5/ADC3_IN15_15") (pintype "passive+no_connect"))
    )
    (net (code "37") (name "/RIGHT_PULSE") (class "Default")
      (node (ref "U3") (pin "21") (pinfunction "PF9/TIM14_CH1/FSMC_CD/ADC3_IN7_21") (pintype "passive+no_connect"))
    )
    (net (code "38") (name "/Right_1") (class "Default")
      (node (ref "D5") (pin "2") (pinfunction "K_2") (pintype "passive"))
      (node (ref "RIGHT_IN") (pin "2") (pinfunction "2_2") (pintype "passive"))
      (node (ref "U4") (pin "13") (pinfunction "4Y_13") (pintype "passive"))
    )
    (net (code "39") (name "/Right_2") (class "Default")
      (node (ref "D6") (pin "2") (pinfunction "K_2") (pintype "passive"))
      (node (ref "RIGHT_IN") (pin "3") (pinfunction "3_3") (pintype "passive"))
      (node (ref "U4") (pin "11") (pinfunction "3Y_11") (pintype "passive"))
    )
    (net (code "40") (name "/SWCLK") (class "Default")
      (node (ref "STLINK") (pin "1") (pinfunction "1_1") (pintype "passive"))
      (node (ref "U3") (pin "109") (pinfunction "PA14/JTCK_SWCLK_109") (pintype "passive"))
    )
    (net (code "41") (name "/SWDIO") (class "Default")
      (node (ref "STLINK") (pin "2") (pinfunction "2_2") (pintype "passive"))
      (node (ref "U3") (pin "105") (pinfunction "PA13/JTMS_SWDIO_105") (pintype "passive"))
    )
    (net (code "42") (name "/U2_RX") (class "Default")
      (node (ref "U3") (pin "37") (pinfunction "PA3/U2_RX/TIM2_CH4/TIM5_CH4/TIM9_CH2/OTG_HS_ULPI_D0/ETH_MII_COL/ADC123_IN3_37") (pintype "passive"))
      (node (ref "UART通讯2") (pin "3") (pinfunction "3_3") (pintype "passive"))
    )
    (net (code "43") (name "/U2_TX") (class "Default")
      (node (ref "U3") (pin "36") (pinfunction "PA2/U2_TX/TIM2_CH3/TIM5_CH3/TIM9_CH1/ETH_MDIO/ADC123_IN2_36") (pintype "passive"))
      (node (ref "UART通讯2") (pin "2") (pinfunction "2_2") (pintype "passive"))
    )
    (net (code "44") (name "/U4_RX") (class "Default")
      (node (ref "U3") (pin "112") (pinfunction "PC11/SPI3_MISO/U3_RX/U4_RX/SDIO_D3/DCMI_D4/I2S3ext_SD_112") (pintype "passive"))
      (node (ref "UART通讯4") (pin "3") (pinfunction "3_3") (pintype "passive"))
    )
    (net (code "45") (name "/U4_TX") (class "Default")
      (node (ref "U3") (pin "111") (pinfunction "PC10/SPI3_SCK/U3_TX/U4_TX/SDIO_D2/DCMI_D8/I2S3_CK_111") (pintype "passive"))
      (node (ref "UART通讯4") (pin "2") (pinfunction "2_2") (pintype "passive"))
    )
    (net (code "46") (name "/U5_RX") (class "Default")
      (node (ref "U3") (pin "116") (pinfunction "PD2/TIM3_ETR/U5_RX/SDIO_CMD/DCMI_D11_116") (pintype "passive"))
      (node (ref "UART通讯5") (pin "3") (pinfunction "3_3") (pintype "passive"))
    )
    (net (code "47") (name "/U5_TX") (class "Default")
      (node (ref "U3") (pin "113") (pinfunction "PC12/SPI3_MOSI/U3_CK/U5_TX/SDIO_CK/DCMI_D9/I2S3_SD_113") (pintype "passive"))
      (node (ref "UART通讯5") (pin "2") (pinfunction "2_2") (pintype "passive"))
    )
    (net (code "48") (name "/U_RX") (class "Default")
      (node (ref "U2") (pin "8") (pinfunction "TXD_8") (pintype "passive"))
      (node (ref "U3") (pin "102") (pinfunction "PA10/TIM1_CH3/U1_RX/OTG_FS_ID/DCMI_D1_102") (pintype "passive"))
    )
    (net (code "49") (name "/U_TX") (class "Default")
      (node (ref "U2") (pin "9") (pinfunction "RXD_9") (pintype "passive"))
      (node (ref "U3") (pin "101") (pinfunction "PA9/TIM1_CH2/U1_TX/I2C3_SMBA/OTG_FS_VBUS/DCMI_D0_101") (pintype "passive"))
    )
    (net (code "50") (name "/VDDA") (class "Default")
      (node (ref "C34") (pin "2") (pinfunction "2_2") (pintype "passive"))
      (node (ref "C35") (pin "2") (pinfunction "2_2") (pintype "passive"))
      (node (ref "R13") (pin "2") (pinfunction "2_2") (pintype "passive"))
      (node (ref "R17") (pin "1") (pinfunction "1_1") (pintype "passive"))
      (node (ref "U3") (pin "33") (pinfunction "VDDA_33") (pintype "passive"))
    )
    (net (code "51") (name "/VREF+") (class "Default")
      (node (ref "C25") (pin "2") (pinfunction "2_2") (pintype "passive"))
      (node (ref "R13") (pin "1") (pinfunction "1_1") (pintype "passive"))
      (node (ref "U3") (pin "32") (pinfunction "Vref+_32") (pintype "passive"))
    )
    (net (code "52") (name "/Z+1") (class "Default")
      (node (ref "左编码器") (pin "7") (pinfunction "7_7") (pintype "passive+no_connect"))
    )
    (net (code "53") (name "/Z+2") (class "Default")
      (node (ref "右编码器") (pin "7") (pinfunction "7_7") (pintype "passive+no_connect"))
    )
    (net (code "54") (name "/Z-1") (class "Default")
      (node (ref "左编码器") (pin "8") (pinfunction "8_8") (pintype "passive+no_connect"))
    )
    (net (code "55") (name "/Z-2") (class "Default")
      (node (ref "右编码器") (pin "8") (pinfunction "8_8") (pintype "passive+no_connect"))
    )
    (net (code "56") (name "GND") (class "Default")
      (node (ref "ATK MODULE") (pin "2") (pinfunction "2_2") (pintype "passive"))
      (node (ref "Battery") (pin "1") (pinfunction "1_1") (pintype "passive"))
      (node (ref "C1") (pin "2") (pinfunction "2_2") (pintype "passive"))
      (node (ref "C10") (pin "2") (pinfunction "2_2") (pintype "passive"))
      (node (ref "C11") (pin "2") (pinfunction "2_2") (pintype "passive"))
      (node (ref "C12") (pin "2") (pinfunction "2_2") (pintype "passive"))
      (node (ref "C13") (pin "2") (pinfunction "2_2") (pintype "passive"))
      (node (ref "C14") (pin "2") (pinfunction "2_2") (pintype "passive"))
      (node (ref "C15") (pin "2") (pinfunction "2_2") (pintype "passive"))
      (node (ref "C16") (pin "2") (pinfunction "2_2") (pintype "passive"))
      (node (ref "C17") (pin "2") (pinfunction "2_2") (pintype "passive"))
      (node (ref "C18") (pin "2") (pinfunction "2_2") (pintype "passive"))
      (node (ref "C19") (pin "2") (pinfunction "2_2") (pintype "passive"))
      (node (ref "C2") (pin "2") (pinfunction "2_2") (pintype "passive"))
      (node (ref "C20") (pin "2") (pinfunction "2_2") (pintype "passive"))
      (node (ref "C21") (pin "2") (pinfunction "2_2") (pintype "passive"))
      (node (ref "C22") (pin "1") (pinfunction "1_1") (pintype "passive"))
      (node (ref "C23") (pin "1") (pinfunction "1_1") (pintype "passive"))
      (node (ref "C24") (pin "1") (pinfunction "1_1") (pintype "passive"))
      (node (ref "C25") (pin "1") (pinfunction "1_1") (pintype "passive"))
      (node (ref "C26") (pin "1") (pinfunction "1_1") (pintype "passive"))
      (node (ref "C27") (pin "1") (pinfunction "1_1") (pintype "passive"))
      (node (ref "C28") (pin "1") (pinfunction "1_1") (pintype "passive"))
      (node (ref "C29") (pin "1") (pinfunction "1_1") (pintype "passive"))
      (node (ref "C3") (pin "2") (pinfunction "2_2") (pintype "passive"))
      (node (ref "C30") (pin "1") (pinfunction "1_1") (pintype "passive"))
      (node (ref "C31") (pin "1") (pinfunction "1_1") (pintype "passive"))
      (node (ref "C32") (pin "2") (pinfunction "2_2") (pintype "passive"))
      (node (ref "C33") (pin "2") (pinfunction "2_2") (pintype "passive"))
      (node (ref "C34") (pin "1") (pinfunction "1_1") (pintype "passive"))
      (node (ref "C35") (pin "1") (pinfunction "1_1") (pintype "passive"))
      (node (ref "C36") (pin "1") (pinfunction "1_1") (pintype "passive"))
      (node (ref "C4") (pin "1") (pinfunction "1_1") (pintype "passive"))
      (node (ref "C5") (pin "2") (pinfunction "2_2") (pintype "passive"))
      (node (ref "C6") (pin "2") (pinfunction "GND_2") (pintype "passive"))
      (node (ref "C7") (pin "1") (pinfunction "1_1") (pintype "passive"))
      (node (ref "C8") (pin "1") (pinfunction "1_1") (pintype "passive"))
      (node (ref "C9") (pin "2") (pinfunction "2_2") (pintype "passive"))
      (node (ref "CSB1") (pin "1") (pinfunction "1_1") (pintype "passive"))
      (node (ref "CSB2") (pin "1") (pinfunction "1_1") (pintype "passive"))
      (node (ref "CSB3") (pin "1") (pinfunction "1_1") (pintype "passive"))
      (node (ref "CSB4") (pin "1") (pinfunction "1_1") (pintype "passive"))
      (node (ref "Charge") (pin "1") (pinfunction "1_1") (pintype "passive"))
      (node (ref "DC_IN") (pin "2") (pinfunction "2_2") (pintype "passive"))
      (node (ref "FDL1") (pin "1") (pinfunction "1_1") (pintype "passive"))
      (node (ref "G D+ D- V") (pin "1") (pinfunction "1_1") (pintype "passive"))
      (node (ref "IIC1") (pin "1") (pinfunction "1_1") (pintype "passive"))
      (node (ref "IIC2") (pin "1") (pinfunction "1_1") (pintype "passive"))
      (node (ref "IIC3") (pin "1") (pinfunction "1_1") (pintype "passive"))
      (node (ref "IIC4") (pin "1") (pinfunction "1_1") (pintype "passive"))
      (node (ref "IIC5") (pin "1") (pinfunction "1_1") (pintype "passive"))
      (node (ref "LEFT_IN") (pin "1") (pinfunction "1_1") (pintype "passive"))
      (node (ref "P1") (pin "1") (pinfunction "1_1") (pintype "passive"))
      (node (ref "P2") (pin "1") (pinfunction "1_1") (pintype "passive"))
      (node (ref "P3") (pin "1") (pinfunction "1_1") (pintype "passive"))
      (node (ref "P4") (pin "1") (pinfunction "1_1") (pintype "passive"))
      (node (ref "P5") (pin "1") (pinfunction "1_1") (pintype "passive"))
      (node (ref "PWR") (pin "K") (pinfunction "K_K") (pintype "passive"))
      (node (ref "R19") (pin "1") (pinfunction "1_1") (pintype "passive"))
      (node (ref "RESET") (pin "2") (pinfunction "2_2") (pintype "passive"))
      (node (ref "RIGHT_IN") (pin "1") (pinfunction "1_1") (pintype "passive"))
      (node (ref "RJ45") (pin "3") (pinfunction "RD+_3") (pintype "passive"))
      (node (ref "RJ46") (pin "3") (pinfunction "RD+_3") (pintype "passive"))
      (node (ref "Remote") (pin "2") (pinfunction "2_2") (pintype "passive"))
      (node (ref "STLINK") (pin "3") (pinfunction "3_3") (pintype "passive"))
      (node (ref "U1") (pin "2") (pinfunction "GND_2") (pintype "passive"))
      (node (ref "U1") (pin "8") (pinfunction "S_8") (pintype "passive"))
      (node (ref "U2") (pin "3") (pinfunction "GND_3") (pintype "passive"))
      (node (ref "U3") (pin "107") (pinfunction "VSS_107") (pintype "passive"))
      (node (ref "U3") (pin "120") (pinfunction "VSS_120") (pintype "passive"))
      (node (ref "U3") (pin "130") (pinfunction "VSS_130") (pintype "passive"))
      (node (ref "U3") (pin "16") (pinfunction "VSS_16") (pintype "passive"))
      (node (ref "U3") (pin "31") (pinfunction "VSSA_31") (pintype "passive"))
      (node (ref "U3") (pin "38") (pinfunction "VSS_38") (pintype "passive"))
      (node (ref "U3") (pin "51") (pinfunction "VSS_51") (pintype "passive"))
      (node (ref "U3") (pin "61") (pinfunction "VSS_61") (pintype "passive"))
      (node (ref "U3") (pin "83") (pinfunction "VSS_83") (pintype "passive"))
      (node (ref "U3") (pin "94") (pinfunction "VSS_94") (pintype "passive"))
      (node (ref "U4") (pin "12") (pinfunction "~{G}_12") (pintype "passive"))
      (node (ref "U4") (pin "4") (pinfunction "G_4") (pintype "passive"))
      (node (ref "U4") (pin "8") (pinfunction "GND_8") (pintype "passive"))
      (node (ref "UART通讯2") (pin "1") (pinfunction "1_1") (pintype "passive"))
      (node (ref "UART通讯4") (pin "1") (pinfunction "1_1") (pintype "passive"))
      (node (ref "UART通讯5") (pin "1") (pinfunction "1_1") (pintype "passive"))
      (node (ref "V1") (pin "2") (pinfunction "GND_2") (pintype "power_in"))
      (node (ref "VR1") (pin "1") (pinfunction "GND_1") (pintype "passive"))
      (node (ref "右编码器") (pin "2") (pinfunction "2_2") (pintype "passive"))
      (node (ref "左编码器") (pin "2") (pinfunction "2_2") (pintype "passive"))
    )
    (net (code "57") (name "Net-(D2-A)") (class "Default")
      (node (ref "D2") (pin "1") (pinfunction "A_1") (pintype "passive"))
      (node (ref "DC_IN") (pin "1") (pinfunction "1_1") (pintype "passive"))
    )
    (net (code "58") (name "Net-(D2-K)") (class "Default")
      (node (ref "C23") (pin "2") (pinfunction "2_2") (pintype "passive"))
      (node (ref "D2") (pin "2") (pinfunction "K_2") (pintype "passive"))
      (node (ref "V1") (pin "1") (pinfunction "IN_1") (pintype "input"))
    )
    (net (code "59") (name "Net-(D3-A)") (class "Default")
      (node (ref "D3") (pin "1") (pinfunction "A_1") (pintype "passive"))
      (node (ref "U3") (pin "136") (pinfunction "PB6/TIM4_CH1/U1_TX/CAN2_TX/I2C1_SCL/DCMI_D5_136") (pintype "passive"))
    )
    (net (code "60") (name "Net-(D4-A)") (class "Default")
      (node (ref "D4") (pin "1") (pinfunction "A_1") (pintype "passive"))
      (node (ref "U3") (pin "137") (pinfunction "PB7/TIM4_CH2/U1_RX/FSMC_NL/I2C1_SDA/DCMI_VSYNC_137") (pintype "passive"))
    )
    (net (code "61") (name "Net-(D5-A)") (class "Default")
      (node (ref "D5") (pin "1") (pinfunction "A_1") (pintype "passive"))
      (node (ref "U3") (pin "96") (pinfunction "PC6/TIM3_CH1/TIM8_CH1/U6_TX/SDIO_D6/DCMI_D0/I2S2_MCK_96") (pintype "passive"))
    )
    (net (code "62") (name "Net-(D6-A)") (class "Default")
      (node (ref "D6") (pin "1") (pinfunction "A_1") (pintype "passive"))
      (node (ref "U3") (pin "97") (pinfunction "PC7/TIM3_CH2/TIM8_CH2/U6_RX/SDIO_D7/DCMI_D1/I2S3_MCK_97") (pintype "passive"))
    )
    (net (code "63") (name "Net-(DS1-PadA)") (class "Default")
      (node (ref "DS1") (pin "A") (pinfunction "A_A") (pintype "passive"))
      (node (ref "R11") (pin "1") (pinfunction "1_1") (pintype "passive"))
    )
    (net (code "64") (name "Net-(DS2-PadA)") (class "Default")
      (node (ref "DS2") (pin "A") (pinfunction "A_A") (pintype "passive"))
      (node (ref "R12") (pin "1") (pinfunction "1_1") (pintype "passive"))
    )
    (net (code "65") (name "Net-(FDL1-Pad2)") (class "Default")
      (node (ref "FDL1") (pin "2") (pinfunction "2_2") (pintype "passive"))
      (node (ref "R9") (pin "1") (pinfunction "1_1") (pintype "passive"))
    )
    (net (code "66") (name "Net-(G D+ D- V-Pad4)") (class "Default")
      (node (ref "G D+ D- V") (pin "4") (pinfunction "4_4") (pintype "passive"))
      (node (ref "R2") (pin "2") (pinfunction "2_2") (pintype "passive"))
    )
    (net (code "67") (name "Net-(PWR-PadA)") (class "Default")
      (node (ref "PWR") (pin "A") (pinfunction "A_A") (pintype "passive"))
      (node (ref "R14") (pin "1") (pinfunction "1_1") (pintype "passive"))
    )
    (net (code "68") (name "Net-(R5-Pad2)") (class "Default")
      (node (ref "R5") (pin "2") (pinfunction "2_2") (pintype "passive"))
      (node (ref "R6") (pin "1") (pinfunction "1_1") (pintype "passive"))
      (node (ref "Remote") (pin "1") (pinfunction "1_1") (pintype "passive"))
    )
    (net (code "69") (name "Net-(R21-Pad1)") (class "Default")
      (node (ref "R21") (pin "1") (pinfunction "1_1") (pintype "passive"))
      (node (ref "左编码器") (pin "1") (pinfunction "1_1") (pintype "passive"))
    )
    (net (code "70") (name "Net-(R22-Pad1)") (class "Default")
      (node (ref "R22") (pin "1") (pinfunction "1_1") (pintype "passive"))
      (node (ref "右编码器") (pin "1") (pinfunction "1_1") (pintype "passive"))
    )
    (net (code "71") (name "Net-(U2-UD+)") (class "Default")
      (node (ref "G D+ D- V") (pin "2") (pinfunction "2_2") (pintype "passive"))
      (node (ref "U2") (pin "1") (pinfunction "UD+_1") (pintype "passive"))
    )
    (net (code "72") (name "Net-(U2-UD-)") (class "Default")
      (node (ref "G D+ D- V") (pin "3") (pinfunction "3_3") (pintype "passive"))
      (node (ref "U2") (pin "2") (pinfunction "UD-_2") (pintype "passive"))
    )
    (net (code "73") (name "Net-(U2-V3.3)") (class "Default")
      (node (ref "C1") (pin "1") (pinfunction "1_1") (pintype "passive"))
      (node (ref "U2") (pin "10") (pinfunction "V3.3_10") (pintype "passive"))
    )
    (net (code "74") (name "Net-(U3-PC14-OSC32_IN)") (class "Default")
      (node (ref "C28") (pin "2") (pinfunction "2_2") (pintype "passive"))
      (node (ref "U3") (pin "8") (pinfunction "PC14-OSC32_IN_8") (pintype "passive"))
      (node (ref "Y1") (pin "1") (pinfunction "OSC1_1") (pintype "passive"))
    )
    (net (code "75") (name "Net-(U3-PC15-OSC32_OUT)") (class "Default")
      (node (ref "C29") (pin "2") (pinfunction "2_2") (pintype "passive"))
      (node (ref "U3") (pin "9") (pinfunction "PC15-OSC32_OUT_9") (pintype "passive"))
      (node (ref "Y1") (pin "2") (pinfunction "OSC2_2") (pintype "passive"))
    )
    (net (code "76") (name "Net-(U3-PDR_ON)") (class "Default")
      (node (ref "R20") (pin "2") (pinfunction "2_2") (pintype "passive"))
      (node (ref "U3") (pin "143") (pinfunction "PDR_ON_143") (pintype "passive"))
    )
    (net (code "77") (name "Net-(U3-PH0-OSC_IN)") (class "Default")
      (node (ref "C31") (pin "2") (pinfunction "2_2") (pintype "passive"))
      (node (ref "R15") (pin "2") (pinfunction "2_2") (pintype "passive"))
      (node (ref "U3") (pin "23") (pinfunction "PH0-OSC_IN_23") (pintype "passive"))
      (node (ref "Y2") (pin "2") (pinfunction "OSC2_2") (pintype "passive"))
    )
    (net (code "78") (name "Net-(U3-PH1-OSC_OUT)") (class "Default")
      (node (ref "C30") (pin "2") (pinfunction "2_2") (pintype "passive"))
      (node (ref "R15") (pin "1") (pinfunction "1_1") (pintype "passive"))
      (node (ref "U3") (pin "24") (pinfunction "PH1-OSC_OUT_24") (pintype "passive"))
      (node (ref "Y2") (pin "1") (pinfunction "OSC1_1") (pintype "passive"))
    )
    (net (code "79") (name "Net-(U3-Vcap_1)") (class "Default")
      (node (ref "C32") (pin "1") (pinfunction "1_1") (pintype "passive"))
      (node (ref "U3") (pin "71") (pinfunction "Vcap_1_71") (pintype "passive"))
    )
    (net (code "80") (name "Net-(U3-Vcap_2)") (class "Default")
      (node (ref "C33") (pin "1") (pinfunction "1_1") (pintype "passive"))
      (node (ref "U3") (pin "106") (pinfunction "Vcap_2_106") (pintype "passive"))
    )
    (net (code "81") (name "VCC3.3M") (class "Default")
      (node (ref "C10") (pin "1") (pinfunction "1_1") (pintype "passive"))
      (node (ref "C11") (pin "1") (pinfunction "1_1") (pintype "passive"))
      (node (ref "C12") (pin "1") (pinfunction "1_1") (pintype "passive"))
      (node (ref "C13") (pin "1") (pinfunction "1_1") (pintype "passive"))
      (node (ref "C14") (pin "1") (pinfunction "1_1") (pintype "passive"))
      (node (ref "C15") (pin "1") (pinfunction "1_1") (pintype "passive"))
      (node (ref "C16") (pin "1") (pinfunction "1_1") (pintype "passive"))
      (node (ref "C17") (pin "1") (pinfunction "1_1") (pintype "passive"))
      (node (ref "C18") (pin "1") (pinfunction "1_1") (pintype "passive"))
      (node (ref "C19") (pin "1") (pinfunction "1_1") (pintype "passive"))
      (node (ref "C20") (pin "1") (pinfunction "1_1") (pintype "passive"))
      (node (ref "C21") (pin "1") (pinfunction "1_1") (pintype "passive"))
      (node (ref "C8") (pin "2") (pinfunction "2_2") (pintype "passive"))
      (node (ref "C9") (pin "1") (pinfunction "1_1") (pintype "passive"))
      (node (ref "R10") (pin "1") (pinfunction "1_1") (pintype "passive"))
      (node (ref "R16") (pin "2") (pinfunction "2_2") (pintype "passive"))
      (node (ref "R17") (pin "2") (pinfunction "2_2") (pintype "passive"))
      (node (ref "R18") (pin "1") (pinfunction "1_1") (pintype "passive"))
      (node (ref "R20") (pin "1") (pinfunction "1_1") (pintype "passive"))
      (node (ref "R3") (pin "2") (pinfunction "2_2") (pintype "passive"))
      (node (ref "R4") (pin "2") (pinfunction "2_2") (pintype "passive"))
      (node (ref "R6") (pin "2") (pinfunction "2_2") (pintype "passive"))
      (node (ref "R7") (pin "1") (pinfunction "1_1") (pintype "passive"))
      (node (ref "Remote") (pin "3") (pinfunction "3_3") (pintype "passive"))
      (node (ref "STLINK") (pin "4") (pinfunction "4_4") (pintype "passive"))
      (node (ref "U3") (pin "108") (pinfunction "VDD_108") (pintype "passive"))
      (node (ref "U3") (pin "121") (pinfunction "VDD_121") (pintype "passive"))
      (node (ref "U3") (pin "131") (pinfunction "VDD_131") (pintype "passive"))
      (node (ref "U3") (pin "144") (pinfunction "VDD_144") (pintype "passive"))
      (node (ref "U3") (pin "17") (pinfunction "VDD_17") (pintype "passive"))
      (node (ref "U3") (pin "30") (pinfunction "VDD_30") (pintype "passive"))
      (node (ref "U3") (pin "39") (pinfunction "VDD_39") (pintype "passive"))
      (node (ref "U3") (pin "52") (pinfunction "VDD_52") (pintype "passive"))
      (node (ref "U3") (pin "6") (pinfunction "VBAT_6") (pintype "passive"))
      (node (ref "U3") (pin "62") (pinfunction "VDD_62") (pintype "passive"))
      (node (ref "U3") (pin "72") (pinfunction "VDD_72") (pintype "passive"))
      (node (ref "U3") (pin "84") (pinfunction "VDD_84") (pintype "passive"))
      (node (ref "U3") (pin "95") (pinfunction "VDD_95") (pintype "passive"))
    )
    (net (code "82") (name "unconnected-(RJ45-CHS_GND-Pad8)") (class "Default")
      (node (ref "RJ45") (pin "8") (pinfunction "CHS_GND_8") (pintype "passive"))
    )
    (net (code "83") (name "unconnected-(RJ45-LED(G)_A-Pad9)") (class "Default")
      (node (ref "RJ45") (pin "9") (pinfunction "LED(G)_A_9") (pintype "passive"))
    )
    (net (code "84") (name "unconnected-(RJ45-LED(G)_K-Pad10)") (class "Default")
      (node (ref "RJ45") (pin "10") (pinfunction "LED(G)_K_10") (pintype "passive"))
    )
    (net (code "85") (name "unconnected-(RJ45-LED(Y)_A-Pad12)") (class "Default")
      (node (ref "RJ45") (pin "12") (pinfunction "LED(Y)_A_12") (pintype "passive"))
    )
    (net (code "86") (name "unconnected-(RJ45-LED(Y)_K-Pad11)") (class "Default")
      (node (ref "RJ45") (pin "11") (pinfunction "LED(Y)_K_11") (pintype "passive"))
    )
    (net (code "87") (name "unconnected-(RJ45-NC-Pad7)") (class "Default")
      (node (ref "RJ45") (pin "7") (pinfunction "NC_7") (pintype "passive"))
    )
    (net (code "88") (name "unconnected-(RJ45-RCT-Pad5)") (class "Default")
      (node (ref "RJ45") (pin "5") (pinfunction "RCT_5") (pintype "passive"))
    )
    (net (code "89") (name "unconnected-(RJ45-RD--Pad6)") (class "Default")
      (node (ref "RJ45") (pin "6") (pinfunction "RD-_6") (pintype "passive"))
    )
    (net (code "90") (name "unconnected-(RJ45-SHILED-Pad13)") (class "Default")
      (node (ref "RJ45") (pin "13") (pinfunction "SHILED_13") (pintype "passive"))
    )
    (net (code "91") (name "unconnected-(RJ45-SHILED-Pad14)") (class "Default")
      (node (ref "RJ45") (pin "14") (pinfunction "SHILED_14") (pintype "passive"))
    )
    (net (code "92") (name "unconnected-(RJ45-TCT-Pad4)") (class "Default")
      (node (ref "RJ45") (pin "4") (pinfunction "TCT_4") (pintype "passive"))
    )
    (net (code "93") (name "unconnected-(RJ46-CHS_GND-Pad8)") (class "Default")
      (node (ref "RJ46") (pin "8") (pinfunction "CHS_GND_8") (pintype "passive"))
    )
    (net (code "94") (name "unconnected-(RJ46-LED(G)_A-Pad9)") (class "Default")
      (node (ref "RJ46") (pin "9") (pinfunction "LED(G)_A_9") (pintype "passive"))
    )
    (net (code "95") (name "unconnected-(RJ46-LED(G)_K-Pad10)") (class "Default")
      (node (ref "RJ46") (pin "10") (pinfunction "LED(G)_K_10") (pintype "passive"))
    )
    (net (code "96") (name "unconnected-(RJ46-LED(Y)_A-Pad12)") (class "Default")
      (node (ref "RJ46") (pin "12") (pinfunction "LED(Y)_A_12") (pintype "passive"))
    )
    (net (code "97") (name "unconnected-(RJ46-LED(Y)_K-Pad11)") (class "Default")
      (node (ref "RJ46") (pin "11") (pinfunction "LED(Y)_K_11") (pintype "passive"))
    )
    (net (code "98") (name "unconnected-(RJ46-NC-Pad7)") (class "Default")
      (node (ref "RJ46") (pin "7") (pinfunction "NC_7") (pintype "passive"))
    )
    (net (code "99") (name "unconnected-(RJ46-RCT-Pad5)") (class "Default")
      (node (ref "RJ46") (pin "5") (pinfunction "RCT_5") (pintype "passive"))
    )
    (net (code "100") (name "unconnected-(RJ46-RD--Pad6)") (class "Default")
      (node (ref "RJ46") (pin "6") (pinfunction "RD-_6") (pintype "passive"))
    )
    (net (code "101") (name "unconnected-(RJ46-SHILED-Pad13)") (class "Default")
      (node (ref "RJ46") (pin "13") (pinfunction "SHILED_13") (pintype "passive"))
    )
    (net (code "102") (name "unconnected-(RJ46-SHILED-Pad14)") (class "Default")
      (node (ref "RJ46") (pin "14") (pinfunction "SHILED_14") (pintype "passive"))
    )
    (net (code "103") (name "unconnected-(RJ46-TCT-Pad4)") (class "Default")
      (node (ref "RJ46") (pin "4") (pinfunction "TCT_4") (pintype "passive"))
    )
    (net (code "104") (name "unconnected-(SRQ-Pad1)") (class "Default")
      (node (ref "SRQ") (pin "1") (pinfunction "1_1") (pintype "passive+no_connect"))
    )
    (net (code "105") (name "unconnected-(SRQ-Pad2)") (class "Default")
      (node (ref "SRQ") (pin "2") (pinfunction "2_2") (pintype "passive+no_connect"))
    )
    (net (code "106") (name "unconnected-(U1-n.c.-Pad5)") (class "Default")
      (node (ref "U1") (pin "5") (pinfunction "n.c._5") (pintype "passive+no_connect"))
    )
    (net (code "107") (name "unconnected-(U2-CTS#-Pad5)") (class "Default")
      (node (ref "U2") (pin "5") (pinfunction "CTS#_5") (pintype "passive+no_connect"))
    )
    (net (code "108") (name "unconnected-(U2-RTS#-Pad4)") (class "Default")
      (node (ref "U2") (pin "4") (pinfunction "RTS#_4") (pintype "passive+no_connect"))
    )
    (net (code "109") (name "unconnected-(U2-TNOW-Pad6)") (class "Default")
      (node (ref "U2") (pin "6") (pinfunction "TNOW_6") (pintype "passive+no_connect"))
    )
    (net (code "110") (name "unconnected-(U3-PA0-WKUP{slash}U2_CTS{slash}U4_TX{slash}ETH_MII_CRS{slash}TIM2_CH1_ETR{slash}TIM5_CH1{slash}TIM8_ETR{slash}ADC123_IN0-Pad34)") (class "Default")
      (node (ref "U3") (pin "34") (pinfunction "PA0-WKUP/U2_CTS/U4_TX/ETH_MII_CRS/TIM2_CH1_ETR/TIM5_CH1/TIM8_ETR/ADC123_IN0_34") (pintype "passive"))
    )
    (net (code "111") (name "unconnected-(U3-PA1{slash}U2_RTS{slash}U4_RX{slash}ETH_RMII_REF_CLK{slash}ETH_MII_RX_CLK{slash}TIM2_CH2{slash}TIM5_CH2{slash}ADC123_IN1-Pad35)") (class "Default")
      (node (ref "U3") (pin "35") (pinfunction "PA1/U2_RTS/U4_RX/ETH_RMII_REF_CLK/ETH_MII_RX_CLK/TIM2_CH2/TIM5_CH2/ADC123_IN1_35") (pintype "passive"))
    )
    (net (code "112") (name "unconnected-(U3-PA4{slash}SPI1_NSS{slash}U2_CK{slash}DCMI_HSYNC{slash}OTG_HS_SOF{slash}I2S3_WS{slash}DAC1_OUT{slash}ADC12_IN4-Pad40)") (class "Default")
      (node (ref "U3") (pin "40") (pinfunction "PA4/SPI1_NSS/U2_CK/DCMI_HSYNC/OTG_HS_SOF/I2S3_WS/DAC1_OUT/ADC12_IN4_40") (pintype "passive+no_connect"))
    )
    (net (code "113") (name "unconnected-(U3-PA6{slash}SPI1_MISO{slash}TIM1_BKIN{slash}TIM3_CH1{slash}TIM8_BKIN{slash}TIM13_CH1{slash}DCMI_PIXCLK{slash}ADC12_IN6-Pad42)") (class "Default")
      (node (ref "U3") (pin "42") (pinfunction "PA6/SPI1_MISO/TIM1_BKIN/TIM3_CH1/TIM8_BKIN/TIM13_CH1/DCMI_PIXCLK/ADC12_IN6_42") (pintype "passive"))
    )
    (net (code "114") (name "unconnected-(U3-PA7{slash}SPI1_MOSI{slash}TIM1_CH1N{slash}TIM3_CH2{slash}TIM8_CH1N{slash}TIM14_CH1{slash}ETH_MII_RX_DV{slash}ETH_RMII_CRS_DV{slash}ADC12_IN7-Pad43)") (class "Default")
      (node (ref "U3") (pin "43") (pinfunction "PA7/SPI1_MOSI/TIM1_CH1N/TIM3_CH2/TIM8_CH1N/TIM14_CH1/ETH_MII_RX_DV/ETH_RMII_CRS_DV/ADC12_IN7_43") (pintype "passive"))
    )
    (net (code "115") (name "unconnected-(U3-PA15{slash}JTDI{slash}SPI1_NSS{slash}SPI3_NSS{slash}TIM2_CH1_ETR{slash}I2S3_WS-Pad110)") (class "Default")
      (node (ref "U3") (pin "110") (pinfunction "PA15/JTDI/SPI1_NSS/SPI3_NSS/TIM2_CH1_ETR/I2S3_WS_110") (pintype "passive"))
    )
    (net (code "116") (name "unconnected-(U3-PB0{slash}TIM1_CH2N{slash}TIM3_CH3{slash}TIM8_CH2N{slash}OTG_HS_ULPI_D1{slash}ETH_MII_RXD2{slash}ADC12_IN8-Pad46)") (class "Default")
      (node (ref "U3") (pin "46") (pinfunction "PB0/TIM1_CH2N/TIM3_CH3/TIM8_CH2N/OTG_HS_ULPI_D1/ETH_MII_RXD2/ADC12_IN8_46") (pintype "passive"))
    )
    (net (code "117") (name "unconnected-(U3-PB1{slash}TIM1_CH3N{slash}TIM3_CH4{slash}TIM8_CH3N{slash}OTG_HS_INTN{slash}ETH_MII_RXD3{slash}ADC12_IN9-Pad47)") (class "Default")
      (node (ref "U3") (pin "47") (pinfunction "PB1/TIM1_CH3N/TIM3_CH4/TIM8_CH3N/OTG_HS_INTN/ETH_MII_RXD3/ADC12_IN9_47") (pintype "passive"))
    )
    (net (code "118") (name "unconnected-(U3-PB3{slash}JTDO{slash}TRACESWO{slash}TIM2_CH2{slash}SPI1_SCK{slash}SPI3_SCK{slash}I2S3_CK-Pad133)") (class "Default")
      (node (ref "U3") (pin "133") (pinfunction "PB3/JTDO/TRACESWO/TIM2_CH2/SPI1_SCK/SPI3_SCK/I2S3_CK_133") (pintype "passive"))
    )
    (net (code "119") (name "unconnected-(U3-PB4{slash}JNTRST{slash}TIM3_CH1{slash}SPI1_MISO{slash}SPI3_MISO{slash}I2S3ext_SD-Pad134)") (class "Default")
      (node (ref "U3") (pin "134") (pinfunction "PB4/JNTRST/TIM3_CH1/SPI1_MISO/SPI3_MISO/I2S3ext_SD_134") (pintype "passive"))
    )
    (net (code "120") (name "unconnected-(U3-PB5{slash}TIM3_CH2{slash}SPI1_MOSI{slash}SPI3_MOSI{slash}CAN2_RX{slash}I2C1_SMBA{slash}OTG_HS_ULPI_D7{slash}ETH_PPS_OUT{slash}DCMI_D10{slash}I2S3_SD-Pad135)") (class "Default")
      (node (ref "U3") (pin "135") (pinfunction "PB5/TIM3_CH2/SPI1_MOSI/SPI3_MOSI/CAN2_RX/I2C1_SMBA/OTG_HS_ULPI_D7/ETH_PPS_OUT/DCMI_D10/I2S3_SD_135") (pintype "passive"))
    )
    (net (code "121") (name "unconnected-(U3-PB14{slash}SPI2_MISO{slash}TIM1_CH2N{slash}TIM8_CH2N{slash}TIM12_CH1{slash}U3_RTS{slash}OTG_HS_DM{slash}I2S2ext_SD-Pad75)") (class "Default")
      (node (ref "U3") (pin "75") (pinfunction "PB14/SPI2_MISO/TIM1_CH2N/TIM8_CH2N/TIM12_CH1/U3_RTS/OTG_HS_DM/I2S2ext_SD_75") (pintype "passive"))
    )
    (net (code "122") (name "unconnected-(U3-PB15{slash}SPI2_MOSI{slash}TIM1_CH3N{slash}TIM8_CH3N{slash}TIM12_CH2{slash}OTG_HS_DP{slash}I2S2_SD-Pad76)") (class "Default")
      (node (ref "U3") (pin "76") (pinfunction "PB15/SPI2_MOSI/TIM1_CH3N/TIM8_CH3N/TIM12_CH2/OTG_HS_DP/I2S2_SD_76") (pintype "passive"))
    )
    (net (code "123") (name "unconnected-(U3-PC1{slash}ETH_MDC{slash}ADC123_IN11-Pad27)") (class "Default")
      (node (ref "U3") (pin "27") (pinfunction "PC1/ETH_MDC/ADC123_IN11_27") (pintype "passive"))
    )
    (net (code "124") (name "unconnected-(U3-PC2{slash}SPI2_MISO{slash}OTG_HS_ULPI_DIR{slash}ETH_MII_TXD2{slash}I2S2ext_SD{slash}ADC123_IN12-Pad28)") (class "Default")
      (node (ref "U3") (pin "28") (pinfunction "PC2/SPI2_MISO/OTG_HS_ULPI_DIR/ETH_MII_TXD2/I2S2ext_SD/ADC123_IN12_28") (pintype "passive"))
    )
    (net (code "125") (name "unconnected-(U3-PC3{slash}SPI2_MOSI{slash}OTG_HS_ULPI_NXT{slash}ETH_MII_TX_CLK{slash}I2S2_SD{slash}ADC123_IN13-Pad29)") (class "Default")
      (node (ref "U3") (pin "29") (pinfunction "PC3/SPI2_MOSI/OTG_HS_ULPI_NXT/ETH_MII_TX_CLK/I2S2_SD/ADC123_IN13_29") (pintype "passive"))
    )
    (net (code "126") (name "unconnected-(U3-PC4{slash}ETH_MII_RXD0{slash}ETH_RMII_RXD0{slash}ADC12_IN14-Pad44)") (class "Default")
      (node (ref "U3") (pin "44") (pinfunction "PC4/ETH_MII_RXD0/ETH_RMII_RXD0/ADC12_IN14_44") (pintype "passive"))
    )
    (net (code "127") (name "unconnected-(U3-PC5{slash}ETH_MII_RXD1{slash}ETH_RMII_RXD1{slash}ADC12_IN15-Pad45)") (class "Default")
      (node (ref "U3") (pin "45") (pinfunction "PC5/ETH_MII_RXD1/ETH_RMII_RXD1/ADC12_IN15_45") (pintype "passive"))
    )
    (net (code "128") (name "unconnected-(U3-PC8{slash}TIM3_CH3{slash}TIM8_CH3{slash}U6_CK{slash}SDIO_D0{slash}DCMI_D2-Pad98)") (class "Default")
      (node (ref "U3") (pin "98") (pinfunction "PC8/TIM3_CH3/TIM8_CH3/U6_CK/SDIO_D0/DCMI_D2_98") (pintype "passive"))
    )
    (net (code "129") (name "unconnected-(U3-PC9{slash}TIM3_CH4{slash}TIM8_CH4{slash}I2C3_SDA{slash}SDIO_D1{slash}DCMI_D3{slash}MCO2{slash}I2S_CKIN-Pad99)") (class "Default")
      (node (ref "U3") (pin "99") (pinfunction "PC9/TIM3_CH4/TIM8_CH4/I2C3_SDA/SDIO_D1/DCMI_D3/MCO2/I2S_CKIN_99") (pintype "passive"))
    )
    (net (code "130") (name "unconnected-(U3-PC13{slash}RTC_AF1-Pad7)") (class "Default")
      (node (ref "U3") (pin "7") (pinfunction "PC13/RTC_AF1_7") (pintype "passive"))
    )
    (net (code "131") (name "unconnected-(U3-PD0{slash}FSMC_D2{slash}CAN1_RX-Pad114)") (class "Default")
      (node (ref "U3") (pin "114") (pinfunction "PD0/FSMC_D2/CAN1_RX_114") (pintype "passive"))
    )
    (net (code "132") (name "unconnected-(U3-PD1{slash}FSMC_D3{slash}CAN1_TX-Pad115)") (class "Default")
      (node (ref "U3") (pin "115") (pinfunction "PD1/FSMC_D3/CAN1_TX_115") (pintype "passive"))
    )
    (net (code "133") (name "unconnected-(U3-PD4{slash}FSMC_NOE{slash}U2_RTS-Pad118)") (class "Default")
      (node (ref "U3") (pin "118") (pinfunction "PD4/FSMC_NOE/U2_RTS_118") (pintype "passive"))
    )
    (net (code "134") (name "unconnected-(U3-PD5{slash}FSMC_NWE{slash}U2_TX-Pad119)") (class "Default")
      (node (ref "U3") (pin "119") (pinfunction "PD5/FSMC_NWE/U2_TX_119") (pintype "passive"))
    )
    (net (code "135") (name "unconnected-(U3-PD6{slash}FSMC_NWAIT{slash}U2_RX-Pad122)") (class "Default")
      (node (ref "U3") (pin "122") (pinfunction "PD6/FSMC_NWAIT/U2_RX_122") (pintype "passive"))
    )
    (net (code "136") (name "unconnected-(U3-PD7{slash}FSMC_NE1{slash}FSMC_NCE2{slash}U2_CK-Pad123)") (class "Default")
      (node (ref "U3") (pin "123") (pinfunction "PD7/FSMC_NE1/FSMC_NCE2/U2_CK_123") (pintype "passive"))
    )
    (net (code "137") (name "unconnected-(U3-PD8{slash}FSMC_D13{slash}U3_TX-Pad77)") (class "Default")
      (node (ref "U3") (pin "77") (pinfunction "PD8/FSMC_D13/U3_TX_77") (pintype "passive"))
    )
    (net (code "138") (name "unconnected-(U3-PD9{slash}FSMC_D14{slash}U3_RX-Pad78)") (class "Default")
      (node (ref "U3") (pin "78") (pinfunction "PD9/FSMC_D14/U3_RX_78") (pintype "passive"))
    )
    (net (code "139") (name "unconnected-(U3-PD10{slash}FSMC_D15{slash}U3_CK-Pad79)") (class "Default")
      (node (ref "U3") (pin "79") (pinfunction "PD10/FSMC_D15/U3_CK_79") (pintype "passive"))
    )
    (net (code "140") (name "unconnected-(U3-PD11{slash}FSMC_A16{slash}FSMC_CLE{slash}U3_CTS-Pad80)") (class "Default")
      (node (ref "U3") (pin "80") (pinfunction "PD11/FSMC_A16/FSMC_CLE/U3_CTS_80") (pintype "passive"))
    )
    (net (code "141") (name "unconnected-(U3-PD12{slash}FSMC_A17{slash}FSMC_ALE{slash}TIM4_CH1{slash}U3_RTS-Pad81)") (class "Default")
      (node (ref "U3") (pin "81") (pinfunction "PD12/FSMC_A17/FSMC_ALE/TIM4_CH1/U3_RTS_81") (pintype "passive"))
    )
    (net (code "142") (name "unconnected-(U3-PD13{slash}FSMC_A18{slash}TIM4_CH2-Pad82)") (class "Default")
      (node (ref "U3") (pin "82") (pinfunction "PD13/FSMC_A18/TIM4_CH2_82") (pintype "passive"))
    )
    (net (code "143") (name "unconnected-(U3-PD14{slash}FSMC_D0{slash}TIM4_CH3-Pad85)") (class "Default")
      (node (ref "U3") (pin "85") (pinfunction "PD14/FSMC_D0/TIM4_CH3_85") (pintype "passive"))
    )
    (net (code "144") (name "unconnected-(U3-PD15{slash}FSMC_D1{slash}TIM4_CH4-Pad86)") (class "Default")
      (node (ref "U3") (pin "86") (pinfunction "PD15/FSMC_D1/TIM4_CH4_86") (pintype "passive"))
    )
    (net (code "145") (name "unconnected-(U3-PE1{slash}FSMC_NBL1{slash}DCMI_D3-Pad142)") (class "Default")
      (node (ref "U3") (pin "142") (pinfunction "PE1/FSMC_NBL1/DCMI_D3_142") (pintype "passive"))
    )
    (net (code "146") (name "unconnected-(U3-PE2{slash}TRACECLK{slash}FSMC_A23{slash}ETH_MII_TXD3-Pad1)") (class "Default")
      (node (ref "U3") (pin "1") (pinfunction "PE2/TRACECLK/FSMC_A23/ETH_MII_TXD3_1") (pintype "passive"))
    )
    (net (code "147") (name "unconnected-(U3-PE3{slash}TRACED0{slash}FSMC_A19-Pad2)") (class "Default")
      (node (ref "U3") (pin "2") (pinfunction "PE3/TRACED0/FSMC_A19_2") (pintype "passive"))
    )
    (net (code "148") (name "unconnected-(U3-PE4{slash}TRACED1{slash}FSMC_A20{slash}DCMI_D4-Pad3)") (class "Default")
      (node (ref "U3") (pin "3") (pinfunction "PE4/TRACED1/FSMC_A20/DCMI_D4_3") (pintype "passive"))
    )
    (net (code "149") (name "unconnected-(U3-PE5{slash}TRACED2{slash}FSMC_A21{slash}TIM9_CH1{slash}DCMI_D6-Pad4)") (class "Default")
      (node (ref "U3") (pin "4") (pinfunction "PE5/TRACED2/FSMC_A21/TIM9_CH1/DCMI_D6_4") (pintype "passive"))
    )
    (net (code "150") (name "unconnected-(U3-PE6{slash}TRACED3{slash}FSMC_A22{slash}TIM9_CH2{slash}DCMI_D7-Pad5)") (class "Default")
      (node (ref "U3") (pin "5") (pinfunction "PE6/TRACED3/FSMC_A22/TIM9_CH2/DCMI_D7_5") (pintype "passive"))
    )
    (net (code "151") (name "unconnected-(U3-PE7{slash}FSMC_D4{slash}TIM1_ETR-Pad58)") (class "Default")
      (node (ref "U3") (pin "58") (pinfunction "PE7/FSMC_D4/TIM1_ETR_58") (pintype "passive"))
    )
    (net (code "152") (name "unconnected-(U3-PE8{slash}FSMC_D5{slash}TIM1_CH1N-Pad59)") (class "Default")
      (node (ref "U3") (pin "59") (pinfunction "PE8/FSMC_D5/TIM1_CH1N_59") (pintype "passive"))
    )
    (net (code "153") (name "unconnected-(U3-PE9{slash}FSMC_D6{slash}TIM1_CH1-Pad60)") (class "Default")
      (node (ref "U3") (pin "60") (pinfunction "PE9/FSMC_D6/TIM1_CH1_60") (pintype "passive"))
    )
    (net (code "154") (name "unconnected-(U3-PE10{slash}FSMC_D7{slash}TIM1_CH2N-Pad63)") (class "Default")
      (node (ref "U3") (pin "63") (pinfunction "PE10/FSMC_D7/TIM1_CH2N_63") (pintype "passive"))
    )
    (net (code "155") (name "unconnected-(U3-PE11{slash}FSMC_D8{slash}TIM1_CH2-Pad64)") (class "Default")
      (node (ref "U3") (pin "64") (pinfunction "PE11/FSMC_D8/TIM1_CH2_64") (pintype "passive"))
    )
    (net (code "156") (name "unconnected-(U3-PE12{slash}FSMC_D9{slash}TIM1_CH3N-Pad65)") (class "Default")
      (node (ref "U3") (pin "65") (pinfunction "PE12/FSMC_D9/TIM1_CH3N_65") (pintype "passive"))
    )
    (net (code "157") (name "unconnected-(U3-PE13{slash}FSMC_D10{slash}TIM1_CH3-Pad66)") (class "Default")
      (node (ref "U3") (pin "66") (pinfunction "PE13/FSMC_D10/TIM1_CH3_66") (pintype "passive"))
    )
    (net (code "158") (name "unconnected-(U3-PE14{slash}FSMC_D11{slash}TIM1_CH4-Pad67)") (class "Default")
      (node (ref "U3") (pin "67") (pinfunction "PE14/FSMC_D11/TIM1_CH4_67") (pintype "passive"))
    )
    (net (code "159") (name "unconnected-(U3-PE15{slash}FSMC_D12{slash}TIM1_BKIN-Pad68)") (class "Default")
      (node (ref "U3") (pin "68") (pinfunction "PE15/FSMC_D12/TIM1_BKIN_68") (pintype "passive"))
    )
    (net (code "160") (name "unconnected-(U3-PF0{slash}FSMC_A0{slash}I2C2_SDA-Pad10)") (class "Default")
      (node (ref "U3") (pin "10") (pinfunction "PF0/FSMC_A0/I2C2_SDA_10") (pintype "passive"))
    )
    (net (code "161") (name "unconnected-(U3-PF1{slash}FSMC_A1{slash}I2C2_SCL-Pad11)") (class "Default")
      (node (ref "U3") (pin "11") (pinfunction "PF1/FSMC_A1/I2C2_SCL_11") (pintype "passive"))
    )
    (net (code "162") (name "unconnected-(U3-PF2{slash}FSMC_A2{slash}I2C2_SMBA-Pad12)") (class "Default")
      (node (ref "U3") (pin "12") (pinfunction "PF2/FSMC_A2/I2C2_SMBA_12") (pintype "passive"))
    )
    (net (code "163") (name "unconnected-(U3-PF3{slash}FSMC_A3{slash}ADC3_IN9-Pad13)") (class "Default")
      (node (ref "U3") (pin "13") (pinfunction "PF3/FSMC_A3/ADC3_IN9_13") (pintype "passive"))
    )
    (net (code "164") (name "unconnected-(U3-PF7{slash}TIM11_CH1{slash}FSMC_NREG{slash}ADC3_IN5-Pad19)") (class "Default")
      (node (ref "U3") (pin "19") (pinfunction "PF7/TIM11_CH1/FSMC_NREG/ADC3_IN5_19") (pintype "passive"))
    )
    (net (code "165") (name "unconnected-(U3-PF10{slash}FSMC_INTR{slash}ADC3_IN8-Pad22)") (class "Default")
      (node (ref "U3") (pin "22") (pinfunction "PF10/FSMC_INTR/ADC3_IN8_22") (pintype "passive+no_connect"))
    )
    (net (code "166") (name "unconnected-(U3-PF11{slash}DCMI_D12-Pad49)") (class "Default")
      (node (ref "U3") (pin "49") (pinfunction "PF11/DCMI_D12_49") (pintype "passive+no_connect"))
    )
    (net (code "167") (name "unconnected-(U3-PF12{slash}FSMC_A6-Pad50)") (class "Default")
      (node (ref "U3") (pin "50") (pinfunction "PF12/FSMC_A6_50") (pintype "passive"))
    )
    (net (code "168") (name "unconnected-(U3-PF13{slash}FSMC_A7-Pad53)") (class "Default")
      (node (ref "U3") (pin "53") (pinfunction "PF13/FSMC_A7_53") (pintype "passive"))
    )
    (net (code "169") (name "unconnected-(U3-PF14{slash}FSMC_A8-Pad54)") (class "Default")
      (node (ref "U3") (pin "54") (pinfunction "PF14/FSMC_A8_54") (pintype "passive"))
    )
    (net (code "170") (name "unconnected-(U3-PF15{slash}FSMC_A9-Pad55)") (class "Default")
      (node (ref "U3") (pin "55") (pinfunction "PF15/FSMC_A9_55") (pintype "passive"))
    )
    (net (code "171") (name "unconnected-(U3-PG0{slash}FSMC_A10-Pad56)") (class "Default")
      (node (ref "U3") (pin "56") (pinfunction "PG0/FSMC_A10_56") (pintype "passive"))
    )
    (net (code "172") (name "unconnected-(U3-PG1{slash}FSMC_A11-Pad57)") (class "Default")
      (node (ref "U3") (pin "57") (pinfunction "PG1/FSMC_A11_57") (pintype "passive"))
    )
    (net (code "173") (name "unconnected-(U3-PG2{slash}FSMC_A12-Pad87)") (class "Default")
      (node (ref "U3") (pin "87") (pinfunction "PG2/FSMC_A12_87") (pintype "passive"))
    )
    (net (code "174") (name "unconnected-(U3-PG3{slash}FSMC_A13-Pad88)") (class "Default")
      (node (ref "U3") (pin "88") (pinfunction "PG3/FSMC_A13_88") (pintype "passive"))
    )
    (net (code "175") (name "unconnected-(U3-PG4{slash}FSMC_A14-Pad89)") (class "Default")
      (node (ref "U3") (pin "89") (pinfunction "PG4/FSMC_A14_89") (pintype "passive"))
    )
    (net (code "176") (name "unconnected-(U3-PG5{slash}FSMC_A15-Pad90)") (class "Default")
      (node (ref "U3") (pin "90") (pinfunction "PG5/FSMC_A15_90") (pintype "passive"))
    )
    (net (code "177") (name "unconnected-(U3-PG6{slash}FSMC_INT2-Pad91)") (class "Default")
      (node (ref "U3") (pin "91") (pinfunction "PG6/FSMC_INT2_91") (pintype "passive"))
    )
    (net (code "178") (name "unconnected-(U3-PG7{slash}FSMC_INT3{slash}U6_CK-Pad92)") (class "Default")
      (node (ref "U3") (pin "92") (pinfunction "PG7/FSMC_INT3/U6_CK_92") (pintype "passive"))
    )
    (net (code "179") (name "unconnected-(U3-PG8{slash}U6_RTS{slash}ETH_PPS_OUT-Pad93)") (class "Default")
      (node (ref "U3") (pin "93") (pinfunction "PG8/U6_RTS/ETH_PPS_OUT_93") (pintype "passive"))
    )
    (net (code "180") (name "unconnected-(U3-PG10{slash}FSMC_NCE4_1{slash}FSMC_NE3-Pad125)") (class "Default")
      (node (ref "U3") (pin "125") (pinfunction "PG10/FSMC_NCE4_1/FSMC_NE3_125") (pintype "passive"))
    )
    (net (code "181") (name "unconnected-(U3-PG11{slash}FSMC_NCE4_2{slash}ETH_MII_TX_EN{slash}ETH_RMII_TX_EN-Pad126)") (class "Default")
      (node (ref "U3") (pin "126") (pinfunction "PG11/FSMC_NCE4_2/ETH_MII_TX_EN/ETH_RMII_TX_EN_126") (pintype "passive"))
    )
    (net (code "182") (name "unconnected-(U3-PG12{slash}FSMC_NE4{slash}U6_RTS-Pad127)") (class "Default")
      (node (ref "U3") (pin "127") (pinfunction "PG12/FSMC_NE4/U6_RTS_127") (pintype "passive"))
    )
    (net (code "183") (name "unconnected-(U3-PG13{slash}FSMC_A24{slash}U6_CTS{slash}ETH_MII_TXD0{slash}ETH_RMII_TXD0-Pad128)") (class "Default")
      (node (ref "U3") (pin "128") (pinfunction "PG13/FSMC_A24/U6_CTS/ETH_MII_TXD0/ETH_RMII_TXD0_128") (pintype "passive"))
    )
    (net (code "184") (name "unconnected-(U3-PG15{slash}U6_CTS{slash}DCMI_D13-Pad132)") (class "Default")
      (node (ref "U3") (pin "132") (pinfunction "PG15/U6_CTS/DCMI_D13_132") (pintype "passive"))
    )
    (net (code "185") (name "unconnected-(右编码器-Pad9)") (class "Default")
      (node (ref "右编码器") (pin "9") (pinfunction "9_9") (pintype "passive+no_connect"))
    )
    (net (code "186") (name "unconnected-(右编码器-Pad10)") (class "Default")
      (node (ref "右编码器") (pin "10") (pinfunction "10_10") (pintype "passive+no_connect"))
    )
    (net (code "187") (name "unconnected-(右编码器-Pad11)") (class "Default")
      (node (ref "右编码器") (pin "11") (pinfunction "11_11") (pintype "passive+no_connect"))
    )
    (net (code "188") (name "unconnected-(右编码器-Pad12)") (class "Default")
      (node (ref "右编码器") (pin "12") (pinfunction "12_12") (pintype "passive+no_connect"))
    )
    (net (code "189") (name "unconnected-(左编码器-Pad9)") (class "Default")
      (node (ref "左编码器") (pin "9") (pinfunction "9_9") (pintype "passive+no_connect"))
    )
    (net (code "190") (name "unconnected-(左编码器-Pad10)") (class "Default")
      (node (ref "左编码器") (pin "10") (pinfunction "10_10") (pintype "passive+no_connect"))
    )
    (net (code "191") (name "unconnected-(左编码器-Pad11)") (class "Default")
      (node (ref "左编码器") (pin "11") (pinfunction "11_11") (pintype "passive+no_connect"))
    )
    (net (code "192") (name "unconnected-(左编码器-Pad12)") (class "Default")
      (node (ref "左编码器") (pin "12") (pinfunction "12_12") (pintype "passive+no_connect"))
    )
  )
)
